# canSlaveV05a.net
KiCad netlist of a schematic drawn in EAGLE
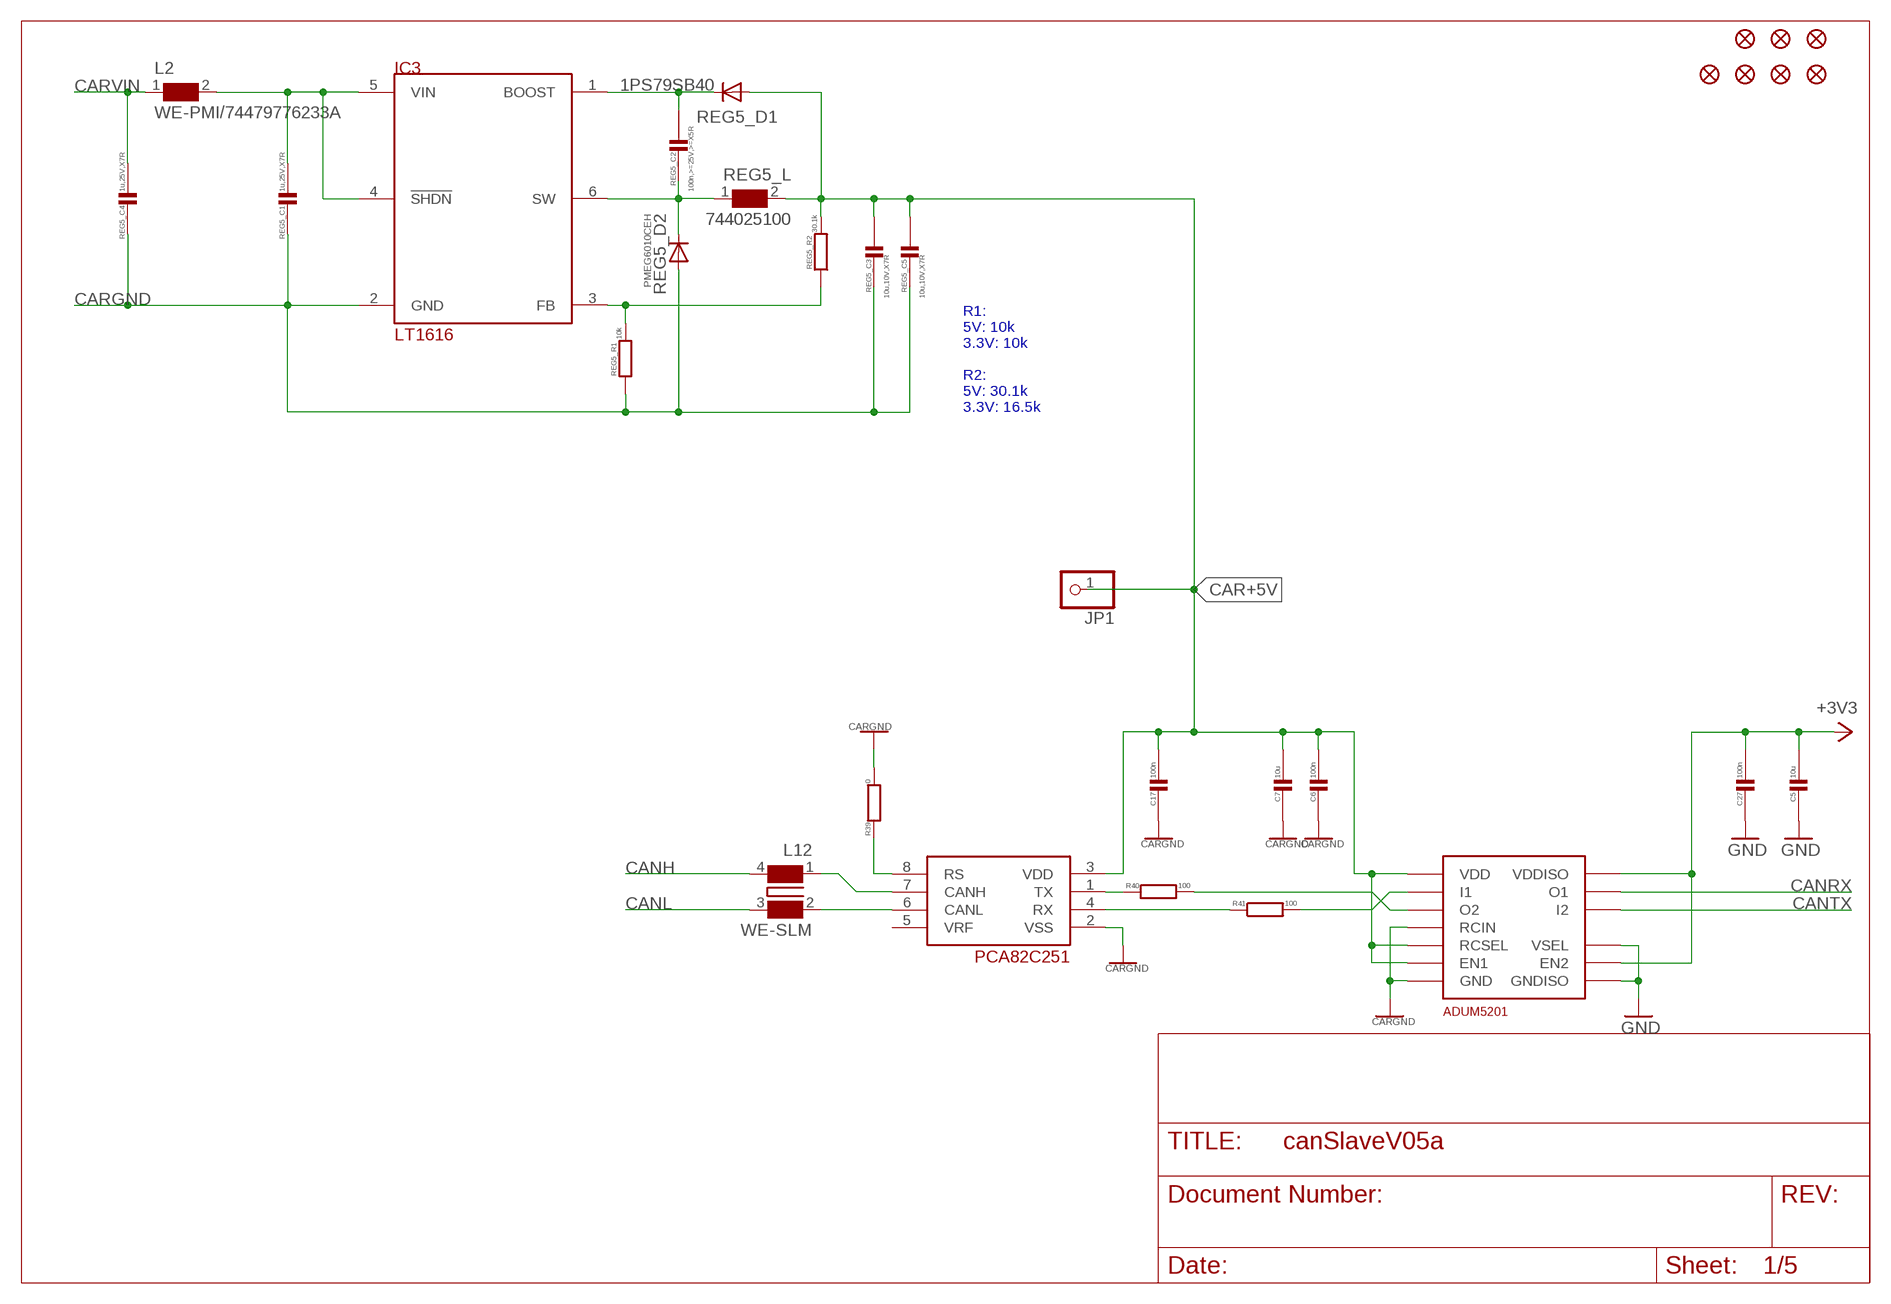
[diagram p0: schematic, sheet 1]
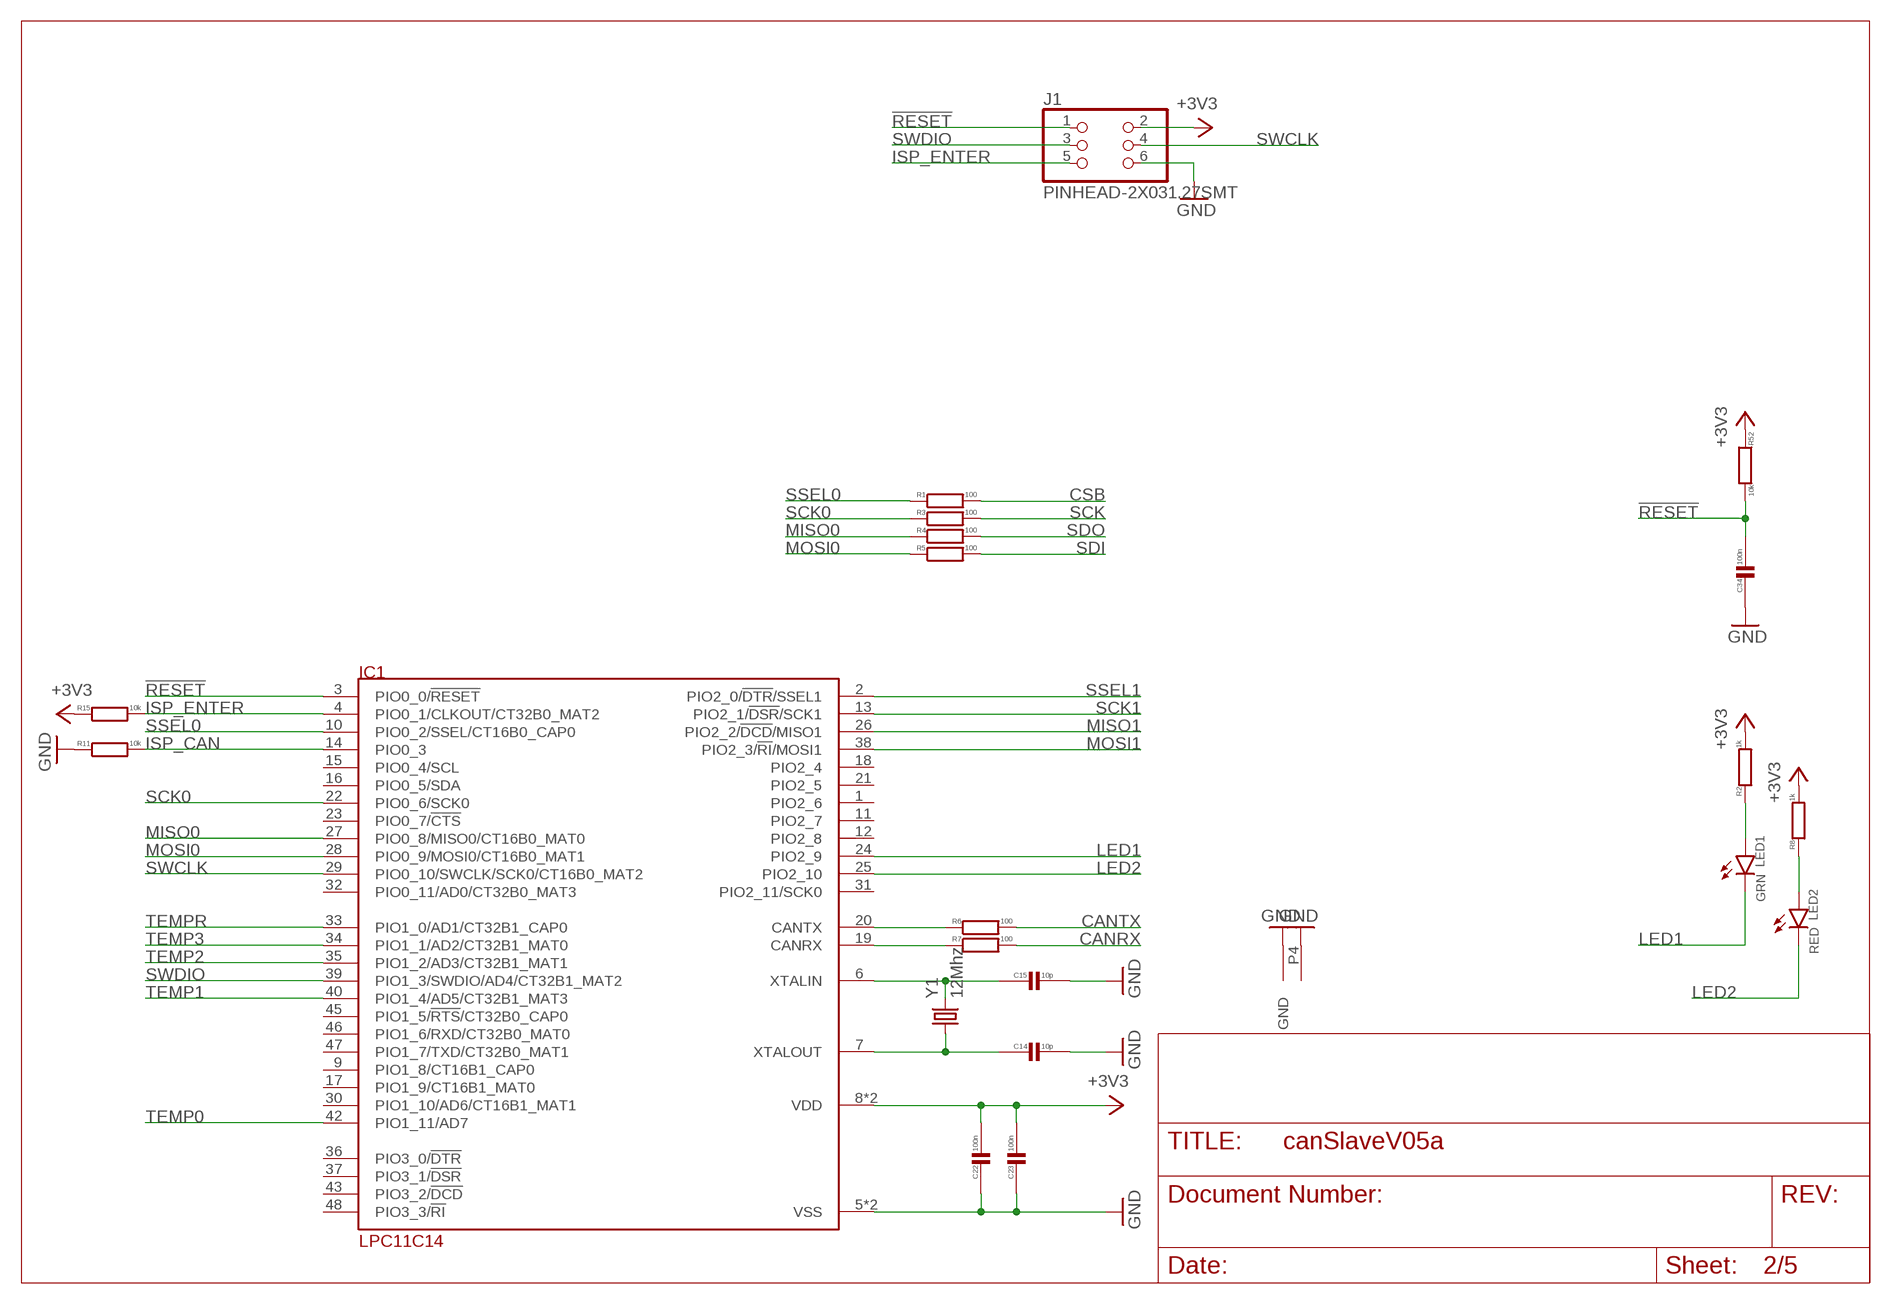
[diagram p1: schematic, sheet 2]
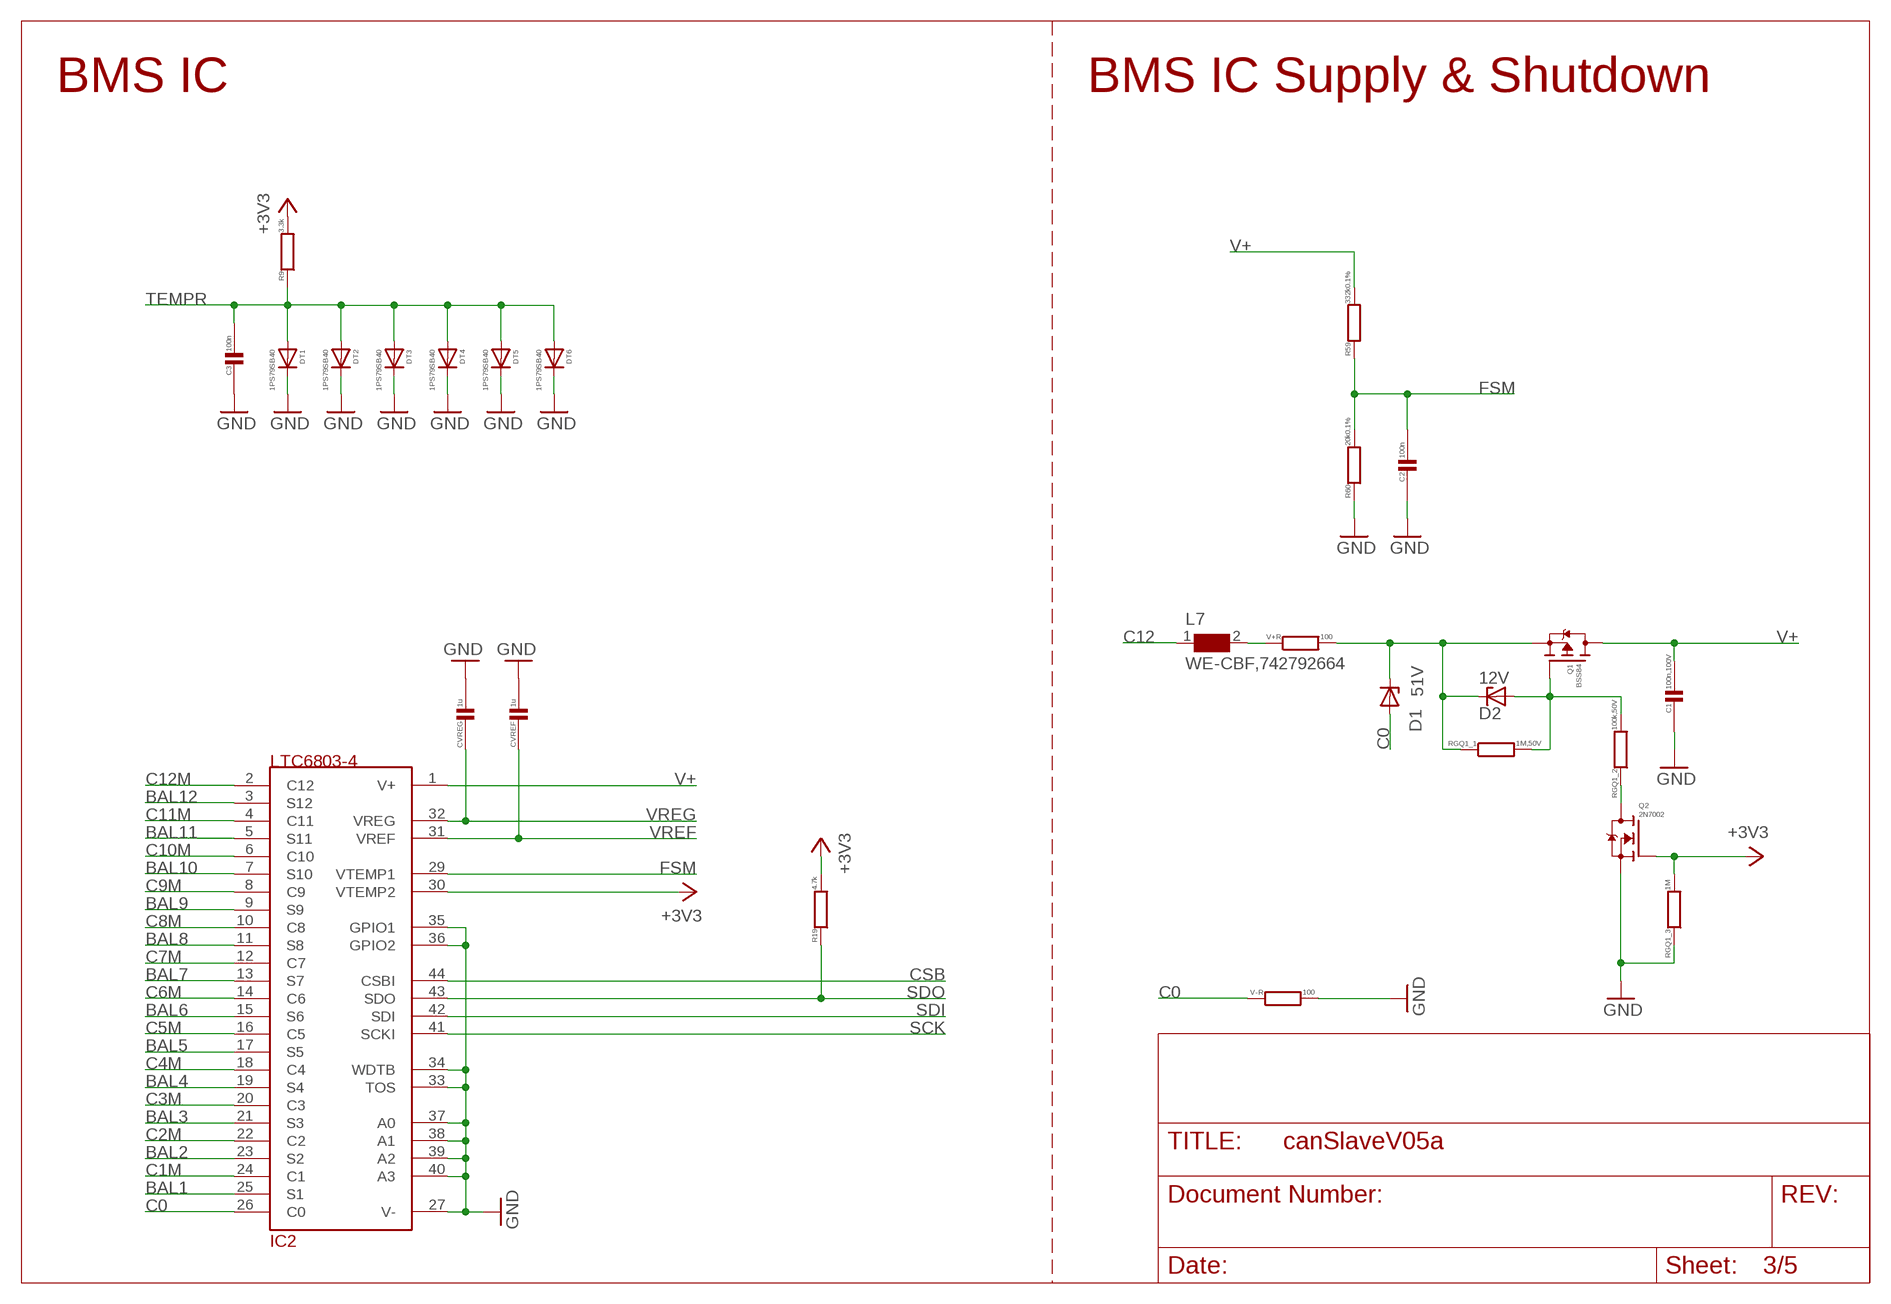
[diagram p2: schematic, sheet 3]
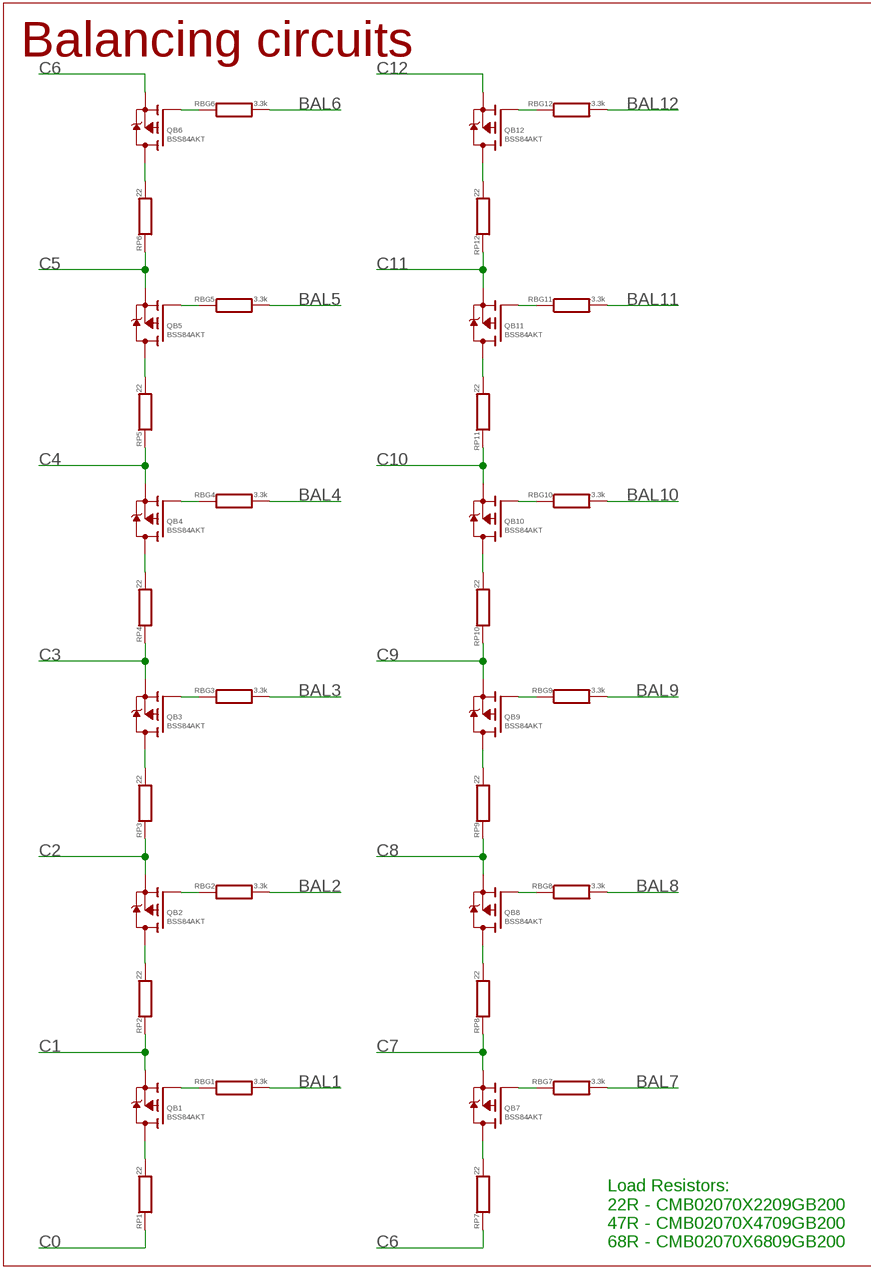
[diagram p3: schematic, sheet 4, part 1 of 2]
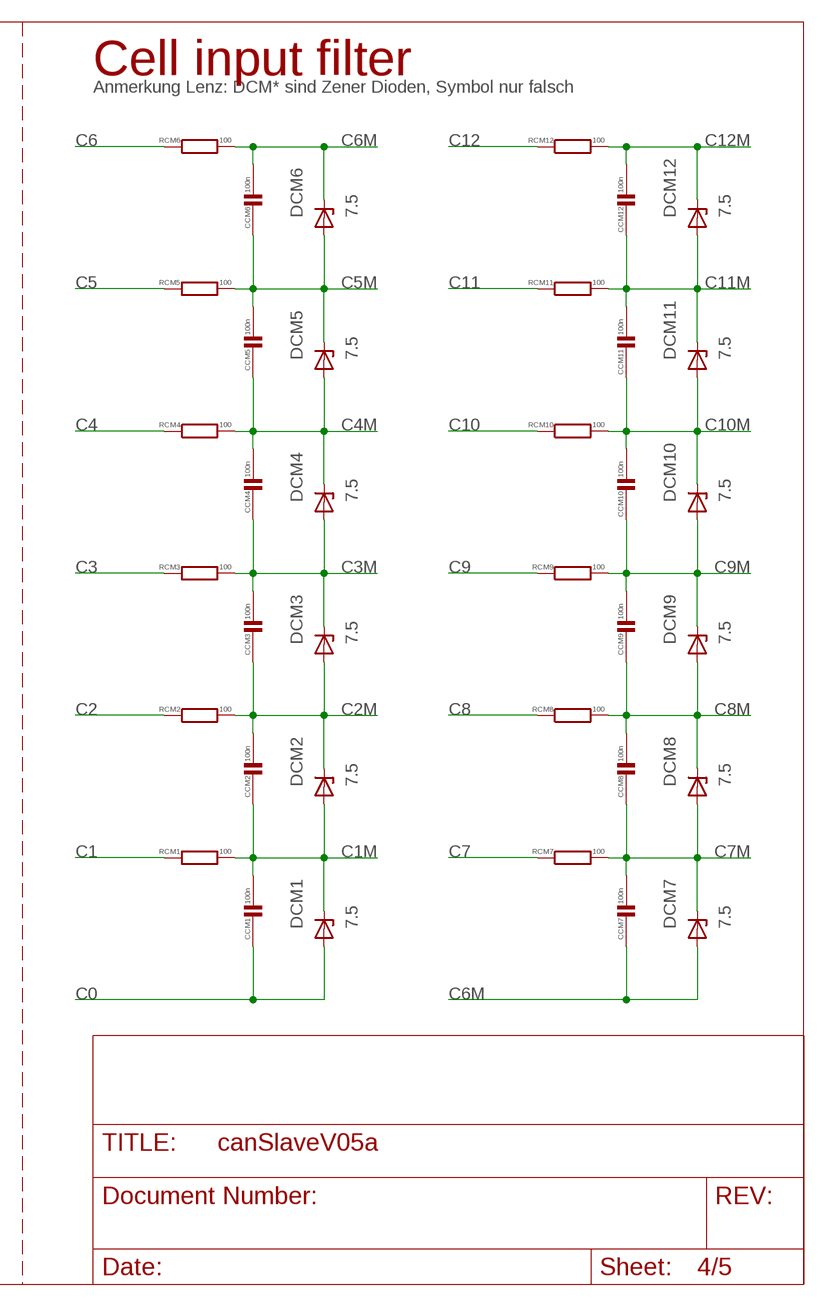
[diagram p4: schematic, sheet 4, part 2 of 2]
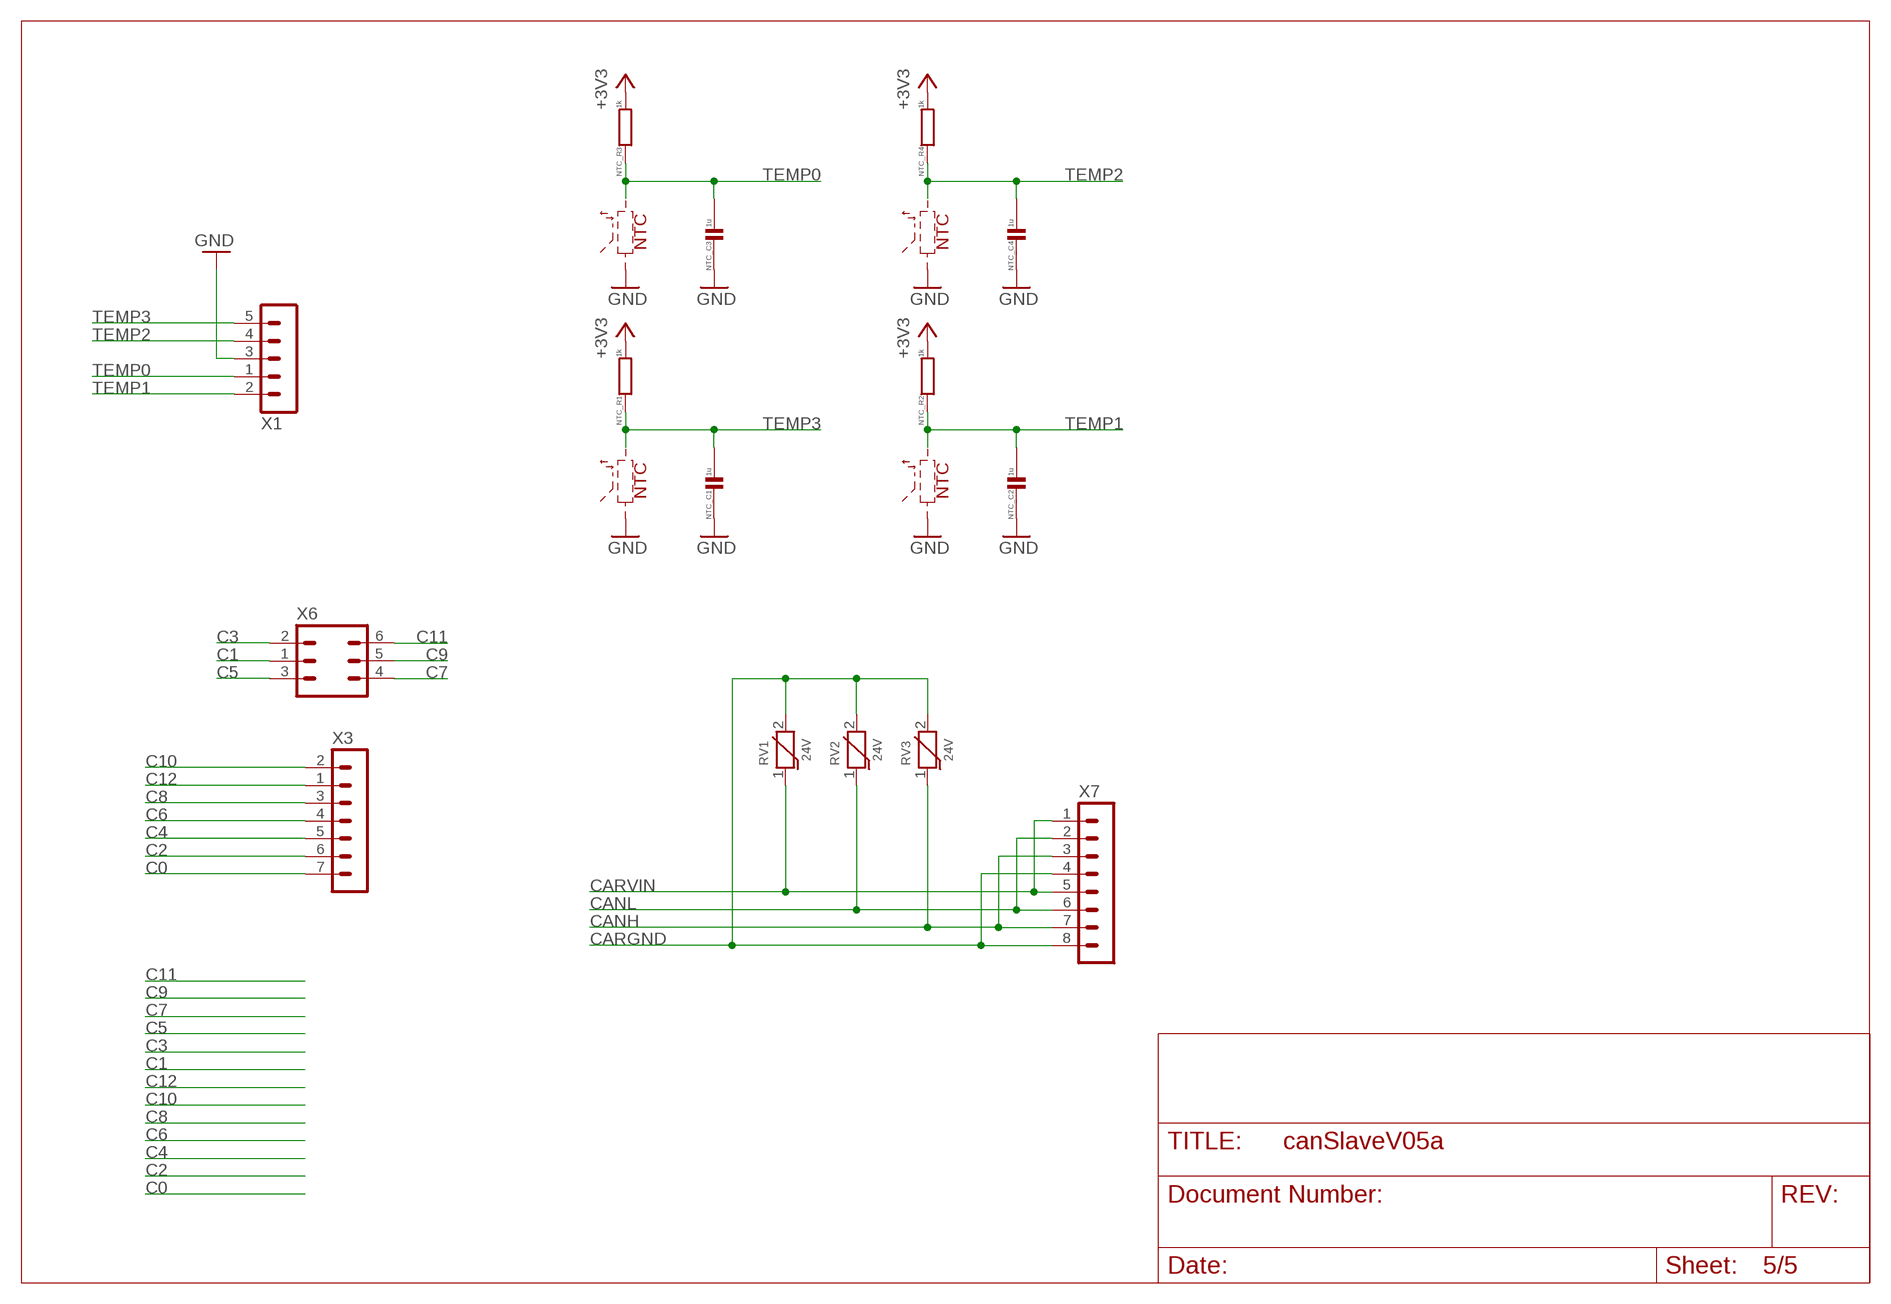
[diagram p5: schematic, sheet 5]

(export (version "E")
  (design (tool "Eeschema 10.0.6"))
  (components
    (comp (ref "C5")
      (value "10u")
      (footprint "eagle-import:C0603")
      (libsource (lib "eagle-import") (part "C0603"))
    )
    (comp (ref "C6")
      (value "100n")
      (footprint "eagle-import:C0402")
      (libsource (lib "eagle-import") (part "C0402"))
    )
    (comp (ref "C7")
      (value "10u")
      (footprint "eagle-import:C0603")
      (libsource (lib "eagle-import") (part "C0603"))
    )
    (comp (ref "C17")
      (value "100n")
      (footprint "eagle-import:C0402")
      (libsource (lib "eagle-import") (part "C0402"))
    )
    (comp (ref "C27")
      (value "100n")
      (footprint "eagle-import:C0402")
      (libsource (lib "eagle-import") (part "C0402"))
    )
    (comp (ref "FID2")
      (value "FIDUCIAL\"\"")
      (footprint "eagle-import:FIDUCIAL_1MM")
      (libsource (lib "eagle-import") (part "FIDUCIAL{dblquote}{dblquote}"))
    )
    (comp (ref "FID3")
      (value "FIDUCIAL\"\"")
      (footprint "eagle-import:FIDUCIAL_1MM")
      (libsource (lib "eagle-import") (part "FIDUCIAL{dblquote}{dblquote}"))
    )
    (comp (ref "FID4")
      (value "FIDUCIAL\"\"")
      (footprint "eagle-import:FIDUCIAL_1MM")
      (libsource (lib "eagle-import") (part "FIDUCIAL{dblquote}{dblquote}"))
    )
    (comp (ref "FID7")
      (value "FIDUCIAL\"\"")
      (footprint "eagle-import:FIDUCIAL_1MM")
      (libsource (lib "eagle-import") (part "FIDUCIAL{dblquote}{dblquote}"))
    )
    (comp (ref "FID8")
      (value "FIDUCIAL\"\"")
      (footprint "eagle-import:FIDUCIAL_1MM")
      (libsource (lib "eagle-import") (part "FIDUCIAL{dblquote}{dblquote}"))
    )
    (comp (ref "FID9")
      (value "FIDUCIAL\"\"")
      (footprint "eagle-import:FIDUCIAL_1MM")
      (libsource (lib "eagle-import") (part "FIDUCIAL{dblquote}{dblquote}"))
    )
    (comp (ref "FID10")
      (value "FIDUCIAL\"\"")
      (footprint "eagle-import:FIDUCIAL_1MM")
      (libsource (lib "eagle-import") (part "FIDUCIAL{dblquote}{dblquote}"))
    )
    (comp (ref "IC3")
      (value "LT1616")
      (footprint "eagle-import:SOT23-6")
      (libsource (lib "eagle-import") (part "LT1616"))
    )
    (comp (ref "IC5")
      (value "PCA82C251")
      (footprint "eagle-import:SO-8")
      (libsource (lib "eagle-import") (part "MCP2551"))
    )
    (comp (ref "JP1")
      (value "PINHD-1X1")
      (footprint "eagle-import:1X01")
      (libsource (lib "eagle-import") (part "PINHD-1X1"))
    )
    (comp (ref "L2")
      (value "WE-PMI/74479776233A")
      (footprint "eagle-import:WE-PMI_0806")
      (libsource (lib "eagle-import") (part "WE-PMI_0806"))
    )
    (comp (ref "L12")
      (value "WE-SLM")
      (footprint "eagle-import:WE-SLM")
      (libsource (lib "eagle-import") (part "WE-SLM"))
    )
    (comp (ref "R39")
      (value "0")
      (footprint "eagle-import:R0402")
      (libsource (lib "eagle-import") (part "R0402"))
    )
    (comp (ref "R40")
      (value "100")
      (footprint "eagle-import:R0402")
      (libsource (lib "eagle-import") (part "R0402"))
    )
    (comp (ref "R41")
      (value "100")
      (footprint "eagle-import:R0402")
      (libsource (lib "eagle-import") (part "R0402"))
    )
    (comp (ref "REG5_C1")
      (value "1u,25V,X7R")
      (footprint "eagle-import:C0805")
      (libsource (lib "eagle-import") (part "C0805"))
    )
    (comp (ref "REG5_C2")
      (value "100n,>=25V,>=X5R")
      (footprint "eagle-import:C0402")
      (libsource (lib "eagle-import") (part "C0402"))
    )
    (comp (ref "REG5_C3")
      (value "10u,10V,X7R")
      (footprint "eagle-import:C0805")
      (libsource (lib "eagle-import") (part "C0805"))
    )
    (comp (ref "REG5_C4")
      (value "1u,25V,X7R")
      (footprint "eagle-import:C0805")
      (libsource (lib "eagle-import") (part "C0805"))
    )
    (comp (ref "REG5_C5")
      (value "10u,10V,X7R")
      (footprint "eagle-import:C0805")
      (libsource (lib "eagle-import") (part "C0805"))
    )
    (comp (ref "REG5_D1")
      (value "1PS79SB40")
      (footprint "eagle-import:SOD523")
      (libsource (lib "eagle-import") (part "DIODE-SOD523"))
    )
    (comp (ref "REG5_D2")
      (value "PMEG6010CEH")
      (footprint "eagle-import:SOD123")
      (libsource (lib "eagle-import") (part "D-SOD123"))
    )
    (comp (ref "REG5_L")
      (value "744025100")
      (footprint "eagle-import:WE-TPC_2828")
      (libsource (lib "eagle-import") (part "WE-TPC_2828"))
    )
    (comp (ref "REG5_R1")
      (value "10k")
      (footprint "eagle-import:R0402")
      (libsource (lib "eagle-import") (part "R0402"))
    )
    (comp (ref "REG5_R2")
      (value "30.1k")
      (footprint "eagle-import:R0402")
      (libsource (lib "eagle-import") (part "R0402"))
    )
    (comp (ref "U$2")
      (value "ADUM5201")
      (footprint "eagle-import:SO16WB")
      (libsource (lib "eagle-import") (part "ADUM5201"))
    )
    (comp (ref "CCM1")
      (value "100n")
      (footprint "eagle-import:C0402")
      (libsource (lib "eagle-import") (part "C0402"))
    )
    (comp (ref "CCM2")
      (value "100n")
      (footprint "eagle-import:C0402")
      (libsource (lib "eagle-import") (part "C0402"))
    )
    (comp (ref "CCM3")
      (value "100n")
      (footprint "eagle-import:C0402")
      (libsource (lib "eagle-import") (part "C0402"))
    )
    (comp (ref "CCM4")
      (value "100n")
      (footprint "eagle-import:C0402")
      (libsource (lib "eagle-import") (part "C0402"))
    )
    (comp (ref "CCM5")
      (value "100n")
      (footprint "eagle-import:C0402")
      (libsource (lib "eagle-import") (part "C0402"))
    )
    (comp (ref "CCM6")
      (value "100n")
      (footprint "eagle-import:C0402")
      (libsource (lib "eagle-import") (part "C0402"))
    )
    (comp (ref "CCM7")
      (value "100n")
      (footprint "eagle-import:C0402")
      (libsource (lib "eagle-import") (part "C0402"))
    )
    (comp (ref "CCM8")
      (value "100n")
      (footprint "eagle-import:C0402")
      (libsource (lib "eagle-import") (part "C0402"))
    )
    (comp (ref "CCM9")
      (value "100n")
      (footprint "eagle-import:C0402")
      (libsource (lib "eagle-import") (part "C0402"))
    )
    (comp (ref "CCM10")
      (value "100n")
      (footprint "eagle-import:C0402")
      (libsource (lib "eagle-import") (part "C0402"))
    )
    (comp (ref "CCM11")
      (value "100n")
      (footprint "eagle-import:C0402")
      (libsource (lib "eagle-import") (part "C0402"))
    )
    (comp (ref "CCM12")
      (value "100n")
      (footprint "eagle-import:C0402")
      (libsource (lib "eagle-import") (part "C0402"))
    )
    (comp (ref "DCM1")
      (value "7.5")
      (footprint "eagle-import:SOD523")
      (libsource (lib "eagle-import") (part "ZENERSOD523"))
    )
    (comp (ref "DCM2")
      (value "7.5")
      (footprint "eagle-import:SOD523")
      (libsource (lib "eagle-import") (part "ZENERSOD523"))
    )
    (comp (ref "DCM3")
      (value "7.5")
      (footprint "eagle-import:SOD523")
      (libsource (lib "eagle-import") (part "ZENERSOD523"))
    )
    (comp (ref "DCM4")
      (value "7.5")
      (footprint "eagle-import:SOD523")
      (libsource (lib "eagle-import") (part "ZENERSOD523"))
    )
    (comp (ref "DCM5")
      (value "7.5")
      (footprint "eagle-import:SOD523")
      (libsource (lib "eagle-import") (part "ZENERSOD523"))
    )
    (comp (ref "DCM6")
      (value "7.5")
      (footprint "eagle-import:SOD523")
      (libsource (lib "eagle-import") (part "ZENERSOD523"))
    )
    (comp (ref "DCM7")
      (value "7.5")
      (footprint "eagle-import:SOD523")
      (libsource (lib "eagle-import") (part "ZENERSOD523"))
    )
    (comp (ref "DCM8")
      (value "7.5")
      (footprint "eagle-import:SOD523")
      (libsource (lib "eagle-import") (part "ZENERSOD523"))
    )
    (comp (ref "DCM9")
      (value "7.5")
      (footprint "eagle-import:SOD523")
      (libsource (lib "eagle-import") (part "ZENERSOD523"))
    )
    (comp (ref "DCM10")
      (value "7.5")
      (footprint "eagle-import:SOD523")
      (libsource (lib "eagle-import") (part "ZENERSOD523"))
    )
    (comp (ref "DCM11")
      (value "7.5")
      (footprint "eagle-import:SOD523")
      (libsource (lib "eagle-import") (part "ZENERSOD523"))
    )
    (comp (ref "DCM12")
      (value "7.5")
      (footprint "eagle-import:SOD523")
      (libsource (lib "eagle-import") (part "ZENERSOD523"))
    )
    (comp (ref "QB1")
      (value "BSS84AKT")
      (footprint "eagle-import:SOT416")
      (libsource (lib "eagle-import") (part "BSS84AKT"))
    )
    (comp (ref "QB2")
      (value "BSS84AKT")
      (footprint "eagle-import:SOT416")
      (libsource (lib "eagle-import") (part "BSS84AKT"))
    )
    (comp (ref "QB3")
      (value "BSS84AKT")
      (footprint "eagle-import:SOT416")
      (libsource (lib "eagle-import") (part "BSS84AKT"))
    )
    (comp (ref "QB4")
      (value "BSS84AKT")
      (footprint "eagle-import:SOT416")
      (libsource (lib "eagle-import") (part "BSS84AKT"))
    )
    (comp (ref "QB5")
      (value "BSS84AKT")
      (footprint "eagle-import:SOT416")
      (libsource (lib "eagle-import") (part "BSS84AKT"))
    )
    (comp (ref "QB6")
      (value "BSS84AKT")
      (footprint "eagle-import:SOT416")
      (libsource (lib "eagle-import") (part "BSS84AKT"))
    )
    (comp (ref "QB7")
      (value "BSS84AKT")
      (footprint "eagle-import:SOT416")
      (libsource (lib "eagle-import") (part "BSS84AKT"))
    )
    (comp (ref "QB8")
      (value "BSS84AKT")
      (footprint "eagle-import:SOT416")
      (libsource (lib "eagle-import") (part "BSS84AKT"))
    )
    (comp (ref "QB9")
      (value "BSS84AKT")
      (footprint "eagle-import:SOT416")
      (libsource (lib "eagle-import") (part "BSS84AKT"))
    )
    (comp (ref "QB10")
      (value "BSS84AKT")
      (footprint "eagle-import:SOT416")
      (libsource (lib "eagle-import") (part "BSS84AKT"))
    )
    (comp (ref "QB11")
      (value "BSS84AKT")
      (footprint "eagle-import:SOT416")
      (libsource (lib "eagle-import") (part "BSS84AKT"))
    )
    (comp (ref "QB12")
      (value "BSS84AKT")
      (footprint "eagle-import:SOT416")
      (libsource (lib "eagle-import") (part "BSS84AKT"))
    )
    (comp (ref "RBG1")
      (value "3.3k")
      (footprint "eagle-import:R0402")
      (libsource (lib "eagle-import") (part "R0402"))
    )
    (comp (ref "RBG2")
      (value "3.3k")
      (footprint "eagle-import:R0402")
      (libsource (lib "eagle-import") (part "R0402"))
    )
    (comp (ref "RBG3")
      (value "3.3k")
      (footprint "eagle-import:R0402")
      (libsource (lib "eagle-import") (part "R0402"))
    )
    (comp (ref "RBG4")
      (value "3.3k")
      (footprint "eagle-import:R0402")
      (libsource (lib "eagle-import") (part "R0402"))
    )
    (comp (ref "RBG5")
      (value "3.3k")
      (footprint "eagle-import:R0402")
      (libsource (lib "eagle-import") (part "R0402"))
    )
    (comp (ref "RBG6")
      (value "3.3k")
      (footprint "eagle-import:R0402")
      (libsource (lib "eagle-import") (part "R0402"))
    )
    (comp (ref "RBG7")
      (value "3.3k")
      (footprint "eagle-import:R0402")
      (libsource (lib "eagle-import") (part "R0402"))
    )
    (comp (ref "RBG8")
      (value "3.3k")
      (footprint "eagle-import:R0402")
      (libsource (lib "eagle-import") (part "R0402"))
    )
    (comp (ref "RBG9")
      (value "3.3k")
      (footprint "eagle-import:R0402")
      (libsource (lib "eagle-import") (part "R0402"))
    )
    (comp (ref "RBG10")
      (value "3.3k")
      (footprint "eagle-import:R0402")
      (libsource (lib "eagle-import") (part "R0402"))
    )
    (comp (ref "RBG11")
      (value "3.3k")
      (footprint "eagle-import:R0402")
      (libsource (lib "eagle-import") (part "R0402"))
    )
    (comp (ref "RBG12")
      (value "3.3k")
      (footprint "eagle-import:R0402")
      (libsource (lib "eagle-import") (part "R0402"))
    )
    (comp (ref "RCM1")
      (value "100")
      (footprint "eagle-import:R0402")
      (libsource (lib "eagle-import") (part "R0402"))
    )
    (comp (ref "RCM2")
      (value "100")
      (footprint "eagle-import:R0402")
      (libsource (lib "eagle-import") (part "R0402"))
    )
    (comp (ref "RCM3")
      (value "100")
      (footprint "eagle-import:R0402")
      (libsource (lib "eagle-import") (part "R0402"))
    )
    (comp (ref "RCM4")
      (value "100")
      (footprint "eagle-import:R0402")
      (libsource (lib "eagle-import") (part "R0402"))
    )
    (comp (ref "RCM5")
      (value "100")
      (footprint "eagle-import:R0402")
      (libsource (lib "eagle-import") (part "R0402"))
    )
    (comp (ref "RCM6")
      (value "100")
      (footprint "eagle-import:R0402")
      (libsource (lib "eagle-import") (part "R0402"))
    )
    (comp (ref "RCM7")
      (value "100")
      (footprint "eagle-import:R0402")
      (libsource (lib "eagle-import") (part "R0402"))
    )
    (comp (ref "RCM8")
      (value "100")
      (footprint "eagle-import:R0402")
      (libsource (lib "eagle-import") (part "R0402"))
    )
    (comp (ref "RCM9")
      (value "100")
      (footprint "eagle-import:R0402")
      (libsource (lib "eagle-import") (part "R0402"))
    )
    (comp (ref "RCM10")
      (value "100")
      (footprint "eagle-import:R0402")
      (libsource (lib "eagle-import") (part "R0402"))
    )
    (comp (ref "RCM11")
      (value "100")
      (footprint "eagle-import:R0402")
      (libsource (lib "eagle-import") (part "R0402"))
    )
    (comp (ref "RCM12")
      (value "100")
      (footprint "eagle-import:R0402")
      (libsource (lib "eagle-import") (part "R0402"))
    )
    (comp (ref "RP1")
      (value "22")
      (footprint "eagle-import:MINI_MELF-0207R")
      (libsource (lib "eagle-import") (part "RMELF-0207R"))
    )
    (comp (ref "RP2")
      (value "22")
      (footprint "eagle-import:MINI_MELF-0207R")
      (libsource (lib "eagle-import") (part "RMELF-0207R"))
    )
    (comp (ref "RP3")
      (value "22")
      (footprint "eagle-import:MINI_MELF-0207R")
      (libsource (lib "eagle-import") (part "RMELF-0207R"))
    )
    (comp (ref "RP4")
      (value "22")
      (footprint "eagle-import:MINI_MELF-0207R")
      (libsource (lib "eagle-import") (part "RMELF-0207R"))
    )
    (comp (ref "RP5")
      (value "22")
      (footprint "eagle-import:MINI_MELF-0207R")
      (libsource (lib "eagle-import") (part "RMELF-0207R"))
    )
    (comp (ref "RP6")
      (value "22")
      (footprint "eagle-import:MINI_MELF-0207R")
      (libsource (lib "eagle-import") (part "RMELF-0207R"))
    )
    (comp (ref "RP7")
      (value "22")
      (footprint "eagle-import:MINI_MELF-0207R")
      (libsource (lib "eagle-import") (part "RMELF-0207R"))
    )
    (comp (ref "RP8")
      (value "22")
      (footprint "eagle-import:MINI_MELF-0207R")
      (libsource (lib "eagle-import") (part "RMELF-0207R"))
    )
    (comp (ref "RP9")
      (value "22")
      (footprint "eagle-import:MINI_MELF-0207R")
      (libsource (lib "eagle-import") (part "RMELF-0207R"))
    )
    (comp (ref "RP10")
      (value "22")
      (footprint "eagle-import:MINI_MELF-0207R")
      (libsource (lib "eagle-import") (part "RMELF-0207R"))
    )
    (comp (ref "RP11")
      (value "22")
      (footprint "eagle-import:MINI_MELF-0207R")
      (libsource (lib "eagle-import") (part "RMELF-0207R"))
    )
    (comp (ref "RP12")
      (value "22")
      (footprint "eagle-import:MINI_MELF-0207R")
      (libsource (lib "eagle-import") (part "RMELF-0207R"))
    )
    (comp (ref "C14")
      (value "10p")
      (footprint "eagle-import:C0402")
      (libsource (lib "eagle-import") (part "C0402"))
    )
    (comp (ref "C15")
      (value "10p")
      (footprint "eagle-import:C0402")
      (libsource (lib "eagle-import") (part "C0402"))
    )
    (comp (ref "C22")
      (value "100n")
      (footprint "eagle-import:C0402")
      (libsource (lib "eagle-import") (part "C0402"))
    )
    (comp (ref "C23")
      (value "100n")
      (footprint "eagle-import:C0402")
      (libsource (lib "eagle-import") (part "C0402"))
    )
    (comp (ref "C34")
      (value "100n")
      (footprint "eagle-import:C0402")
      (libsource (lib "eagle-import") (part "C0402"))
    )
    (comp (ref "IC1")
      (value "LPC11C14")
      (footprint "eagle-import:LQFP48")
      (libsource (lib "eagle-import") (part "LPC11C1X"))
    )
    (comp (ref "J1")
      (value "PINHEAD-2X031.27SMT")
      (footprint "eagle-import:2X03_1.27MM_SMT")
      (libsource (lib "eagle-import") (part "PINHEAD-2X031.27SMT"))
    )
    (comp (ref "LED1")
      (value "GRN")
      (footprint "eagle-import:CHIPLED_0603")
      (libsource (lib "eagle-import") (part "LED0603"))
    )
    (comp (ref "LED2")
      (value "RED")
      (footprint "eagle-import:CHIPLED_0603")
      (libsource (lib "eagle-import") (part "LED0603"))
    )
    (comp (ref "R1")
      (value "100")
      (footprint "eagle-import:R0402")
      (libsource (lib "eagle-import") (part "R0402"))
    )
    (comp (ref "R2")
      (value "1k")
      (footprint "eagle-import:R0402")
      (libsource (lib "eagle-import") (part "R0402"))
    )
    (comp (ref "R3")
      (value "100")
      (footprint "eagle-import:R0402")
      (libsource (lib "eagle-import") (part "R0402"))
    )
    (comp (ref "R4")
      (value "100")
      (footprint "eagle-import:R0402")
      (libsource (lib "eagle-import") (part "R0402"))
    )
    (comp (ref "R5")
      (value "100")
      (footprint "eagle-import:R0402")
      (libsource (lib "eagle-import") (part "R0402"))
    )
    (comp (ref "R6")
      (value "100")
      (footprint "eagle-import:R0402")
      (libsource (lib "eagle-import") (part "R0402"))
    )
    (comp (ref "R7")
      (value "100")
      (footprint "eagle-import:R0402")
      (libsource (lib "eagle-import") (part "R0402"))
    )
    (comp (ref "R8")
      (value "1k")
      (footprint "eagle-import:R0402")
      (libsource (lib "eagle-import") (part "R0402"))
    )
    (comp (ref "R11")
      (value "10k")
      (footprint "eagle-import:R0402")
      (libsource (lib "eagle-import") (part "R0402"))
    )
    (comp (ref "R15")
      (value "10k")
      (footprint "eagle-import:R0402")
      (libsource (lib "eagle-import") (part "R0402"))
    )
    (comp (ref "R52")
      (value "10k")
      (footprint "eagle-import:R0402")
      (libsource (lib "eagle-import") (part "R0402"))
    )
    (comp (ref "Y1")
      (value "12Mhz")
      (footprint "eagle-import:MT")
      (libsource (lib "eagle-import") (part "CRYSTAL43.2X2.5"))
    )
    (comp (ref "NTC_C1")
      (value "1u")
      (footprint "eagle-import:C0402")
      (libsource (lib "eagle-import") (part "C0402"))
    )
    (comp (ref "NTC_C2")
      (value "1u")
      (footprint "eagle-import:C0402")
      (libsource (lib "eagle-import") (part "C0402"))
    )
    (comp (ref "NTC_C3")
      (value "1u")
      (footprint "eagle-import:C0402")
      (libsource (lib "eagle-import") (part "C0402"))
    )
    (comp (ref "NTC_C4")
      (value "1u")
      (footprint "eagle-import:C0402")
      (libsource (lib "eagle-import") (part "C0402"))
    )
    (comp (ref "NTC_R1")
      (value "1k")
      (footprint "eagle-import:R0402")
      (libsource (lib "eagle-import") (part "R0402"))
    )
    (comp (ref "NTC_R2")
      (value "1k")
      (footprint "eagle-import:R0402")
      (libsource (lib "eagle-import") (part "R0402"))
    )
    (comp (ref "NTC_R3")
      (value "1k")
      (footprint "eagle-import:R0402")
      (libsource (lib "eagle-import") (part "R0402"))
    )
    (comp (ref "NTC_R4")
      (value "1k")
      (footprint "eagle-import:R0402")
      (libsource (lib "eagle-import") (part "R0402"))
    )
    (comp (ref "RV1")
      (value "24V")
      (footprint "eagle-import:R0805")
      (libsource (lib "eagle-import") (part "VARISTOR0805"))
    )
    (comp (ref "RV2")
      (value "24V")
      (footprint "eagle-import:R0603")
      (libsource (lib "eagle-import") (part "VARISTOR0603"))
    )
    (comp (ref "RV3")
      (value "24V")
      (footprint "eagle-import:R0603")
      (libsource (lib "eagle-import") (part "VARISTOR0603"))
    )
    (comp (ref "X1")
      (value "HEADER_POS5_43650-0509")
      (footprint "eagle-import:43650-0509")
      (libsource (lib "eagle-import") (part "HEADER_POS5_?43650-0509"))
    )
    (comp (ref "X3")
      (value "HEADER_POS7_43650-0709")
      (footprint "eagle-import:43650-0709")
      (libsource (lib "eagle-import") (part "HEADER_POS7_?43650-0709"))
    )
    (comp (ref "X6")
      (value "HEADER_POS6_43650-0609")
      (footprint "eagle-import:43650-0609")
      (libsource (lib "eagle-import") (part "HEADER_POS6_?43650-0609"))
    )
    (comp (ref "X7")
      (value "HEADER_POS8_43045-0800")
      (footprint "eagle-import:43045-0800")
      (libsource (lib "eagle-import") (part "HEADER_POS8_?43045-0800"))
    )
    (comp (ref "C1")
      (value "100n,100V")
      (footprint "eagle-import:C0603")
      (libsource (lib "eagle-import") (part "C0603"))
    )
    (comp (ref "C2")
      (value "100n")
      (footprint "eagle-import:C0402")
      (libsource (lib "eagle-import") (part "C0402"))
    )
    (comp (ref "C3")
      (value "100n")
      (footprint "eagle-import:C0402")
      (libsource (lib "eagle-import") (part "C0402"))
    )
    (comp (ref "CVREF")
      (value "1u")
      (footprint "eagle-import:C0402")
      (libsource (lib "eagle-import") (part "C0402"))
    )
    (comp (ref "CVREG")
      (value "1u")
      (footprint "eagle-import:C0402")
      (libsource (lib "eagle-import") (part "C0402"))
    )
    (comp (ref "D1")
      (value "51V")
      (footprint "eagle-import:SOD323-L")
      (libsource (lib "eagle-import") (part "ZENERSOD323"))
    )
    (comp (ref "D2")
      (value "12V")
      (footprint "eagle-import:SOD323-L")
      (libsource (lib "eagle-import") (part "ZENERSOD323"))
    )
    (comp (ref "DT1")
      (value "1PS79SB40")
      (footprint "eagle-import:SOD523")
      (libsource (lib "eagle-import") (part "DIODE-SOD523"))
    )
    (comp (ref "DT2")
      (value "1PS79SB40")
      (footprint "eagle-import:SOD523")
      (libsource (lib "eagle-import") (part "DIODE-SOD523"))
    )
    (comp (ref "DT3")
      (value "1PS79SB40")
      (footprint "eagle-import:SOD523")
      (libsource (lib "eagle-import") (part "DIODE-SOD523"))
    )
    (comp (ref "DT4")
      (value "1PS79SB40")
      (footprint "eagle-import:SOD523")
      (libsource (lib "eagle-import") (part "DIODE-SOD523"))
    )
    (comp (ref "DT5")
      (value "1PS79SB40")
      (footprint "eagle-import:SOD523")
      (libsource (lib "eagle-import") (part "DIODE-SOD523"))
    )
    (comp (ref "DT6")
      (value "1PS79SB40")
      (footprint "eagle-import:SOD523")
      (libsource (lib "eagle-import") (part "DIODE-SOD523"))
    )
    (comp (ref "IC2")
      (value "LTC6803-4")
      (footprint "eagle-import:44SSOP")
      (libsource (lib "eagle-import") (part "LTC6803-4"))
    )
    (comp (ref "L7")
      (value "WE-CBF,742792664")
      (footprint "eagle-import:0603")
      (libsource (lib "eagle-import") (part "WE-CBF_0603"))
    )
    (comp (ref "Q1")
      (value "BSS84")
      (footprint "eagle-import:SOT23")
      (libsource (lib "eagle-import") (part "BSS84"))
    )
    (comp (ref "Q2")
      (value "2N7002")
      (footprint "eagle-import:SOT23")
      (libsource (lib "eagle-import") (part "2N7002"))
    )
    (comp (ref "R9")
      (value "3.3k")
      (footprint "eagle-import:R0603")
      (libsource (lib "eagle-import") (part "R0603"))
    )
    (comp (ref "R19")
      (value "4.7k")
      (footprint "eagle-import:R0402")
      (libsource (lib "eagle-import") (part "R0402"))
    )
    (comp (ref "R59")
      (value "332k0.1%")
      (footprint "eagle-import:R0603")
      (libsource (lib "eagle-import") (part "R0603"))
    )
    (comp (ref "R60")
      (value "20k0.1%")
      (footprint "eagle-import:R0402")
      (libsource (lib "eagle-import") (part "R0402"))
    )
    (comp (ref "RGQ1_1")
      (value "1M,50V")
      (footprint "eagle-import:R0603")
      (libsource (lib "eagle-import") (part "R0603"))
    )
    (comp (ref "RGQ1_2")
      (value "100k,50V")
      (footprint "eagle-import:R0603")
      (libsource (lib "eagle-import") (part "R0603"))
    )
    (comp (ref "RGQ1_3")
      (value "1M")
      (footprint "eagle-import:R0402")
      (libsource (lib "eagle-import") (part "R0402"))
    )
    (comp (ref "V+R")
      (value "100")
      (footprint "eagle-import:R0603")
      (libsource (lib "eagle-import") (part "R0603"))
    )
    (comp (ref "V-R")
      (value "100")
      (footprint "eagle-import:R0603")
      (libsource (lib "eagle-import") (part "R0603"))
    )
  )
  (nets
    (net (code "1") (name "+3V3") (class "Default")
      (node (ref "C22") (pin "1") (pinfunction "1_1") (pintype "passive"))
      (node (ref "C23") (pin "1") (pinfunction "1_1") (pintype "passive"))
      (node (ref "C27") (pin "1") (pinfunction "1_1") (pintype "passive"))
      (node (ref "C5") (pin "1") (pinfunction "1_1") (pintype "passive"))
      (node (ref "IC1") (pin "44") (pinfunction "VDD_44") (pintype "bidirectional"))
      (node (ref "IC1") (pin "8") (pinfunction "VDD_8") (pintype "bidirectional"))
      (node (ref "IC2") (pin "30") (pinfunction "VTEMP2_30") (pintype "bidirectional"))
      (node (ref "J1") (pin "2") (pinfunction "2_2") (pintype "passive"))
      (node (ref "NTC_R1") (pin "2") (pinfunction "2_2") (pintype "passive"))
      (node (ref "NTC_R2") (pin "2") (pinfunction "2_2") (pintype "passive"))
      (node (ref "NTC_R3") (pin "2") (pinfunction "2_2") (pintype "passive"))
      (node (ref "NTC_R4") (pin "2") (pinfunction "2_2") (pintype "passive"))
      (node (ref "Q2") (pin "1") (pinfunction "G_1") (pintype "passive"))
      (node (ref "R15") (pin "1") (pinfunction "1_1") (pintype "passive"))
      (node (ref "R19") (pin "2") (pinfunction "2_2") (pintype "passive"))
      (node (ref "R2") (pin "2") (pinfunction "2_2") (pintype "passive"))
      (node (ref "R52") (pin "1") (pinfunction "1_1") (pintype "passive"))
      (node (ref "R8") (pin "2") (pinfunction "2_2") (pintype "passive"))
      (node (ref "R9") (pin "2") (pinfunction "2_2") (pintype "passive"))
      (node (ref "RGQ1_3") (pin "2") (pinfunction "2_2") (pintype "passive"))
      (node (ref "U$2") (pin "P$10") (pinfunction "EN2_P$10") (pintype "bidirectional"))
      (node (ref "U$2") (pin "P$16") (pinfunction "VDDISO_P$16") (pintype "bidirectional"))
    )
    (net (code "2") (name "BAL1") (class "Default")
      (node (ref "IC2") (pin "25") (pinfunction "S1_25") (pintype "bidirectional"))
      (node (ref "RBG1") (pin "2") (pinfunction "2_2") (pintype "passive"))
    )
    (net (code "3") (name "BAL2") (class "Default")
      (node (ref "IC2") (pin "23") (pinfunction "S2_23") (pintype "bidirectional"))
      (node (ref "RBG2") (pin "2") (pinfunction "2_2") (pintype "passive"))
    )
    (net (code "4") (name "BAL3") (class "Default")
      (node (ref "IC2") (pin "21") (pinfunction "S3_21") (pintype "bidirectional"))
      (node (ref "RBG3") (pin "2") (pinfunction "2_2") (pintype "passive"))
    )
    (net (code "5") (name "BAL4") (class "Default")
      (node (ref "IC2") (pin "19") (pinfunction "S4_19") (pintype "bidirectional"))
      (node (ref "RBG4") (pin "2") (pinfunction "2_2") (pintype "passive"))
    )
    (net (code "6") (name "BAL5") (class "Default")
      (node (ref "IC2") (pin "17") (pinfunction "S5_17") (pintype "bidirectional"))
      (node (ref "RBG5") (pin "2") (pinfunction "2_2") (pintype "passive"))
    )
    (net (code "7") (name "BAL6") (class "Default")
      (node (ref "IC2") (pin "15") (pinfunction "S6_15") (pintype "bidirectional"))
      (node (ref "RBG6") (pin "2") (pinfunction "2_2") (pintype "passive"))
    )
    (net (code "8") (name "BAL7") (class "Default")
      (node (ref "IC2") (pin "13") (pinfunction "S7_13") (pintype "bidirectional"))
      (node (ref "RBG7") (pin "2") (pinfunction "2_2") (pintype "passive"))
    )
    (net (code "9") (name "BAL8") (class "Default")
      (node (ref "IC2") (pin "11") (pinfunction "S8_11") (pintype "bidirectional"))
      (node (ref "RBG8") (pin "2") (pinfunction "2_2") (pintype "passive"))
    )
    (net (code "10") (name "BAL9") (class "Default")
      (node (ref "IC2") (pin "9") (pinfunction "S9_9") (pintype "bidirectional"))
      (node (ref "RBG9") (pin "2") (pinfunction "2_2") (pintype "passive"))
    )
    (net (code "11") (name "BAL10") (class "Default")
      (node (ref "IC2") (pin "7") (pinfunction "S10_7") (pintype "bidirectional"))
      (node (ref "RBG10") (pin "2") (pinfunction "2_2") (pintype "passive"))
    )
    (net (code "12") (name "BAL11") (class "Default")
      (node (ref "IC2") (pin "5") (pinfunction "S11_5") (pintype "bidirectional"))
      (node (ref "RBG11") (pin "2") (pinfunction "2_2") (pintype "passive"))
    )
    (net (code "13") (name "BAL12") (class "Default")
      (node (ref "IC2") (pin "3") (pinfunction "S12_3") (pintype "bidirectional"))
      (node (ref "RBG12") (pin "2") (pinfunction "2_2") (pintype "passive"))
    )
    (net (code "14") (name "C0") (class "Default")
      (node (ref "CCM1") (pin "2") (pinfunction "2_2") (pintype "passive"))
      (node (ref "D1") (pin "A") (pinfunction "A_A") (pintype "passive"))
      (node (ref "DCM1") (pin "A") (pinfunction "A_A") (pintype "passive"))
      (node (ref "IC2") (pin "26") (pinfunction "C0_26") (pintype "bidirectional"))
      (node (ref "RP1") (pin "1") (pinfunction "1_1") (pintype "passive"))
      (node (ref "V-R") (pin "1") (pinfunction "1_1") (pintype "passive"))
      (node (ref "X3") (pin "7") (pinfunction "7_7") (pintype "passive"))
    )
    (net (code "15") (name "C1") (class "Default")
      (node (ref "QB1") (pin "2") (pinfunction "S_2") (pintype "passive"))
      (node (ref "RCM1") (pin "1") (pinfunction "1_1") (pintype "passive"))
      (node (ref "RP2") (pin "1") (pinfunction "1_1") (pintype "passive"))
      (node (ref "X6") (pin "1") (pinfunction "2_1") (pintype "passive"))
    )
    (net (code "16") (name "C1M") (class "Default")
      (node (ref "CCM1") (pin "1") (pinfunction "1_1") (pintype "passive"))
      (node (ref "CCM2") (pin "2") (pinfunction "2_2") (pintype "passive"))
      (node (ref "DCM1") (pin "C") (pinfunction "C_C") (pintype "passive"))
      (node (ref "DCM2") (pin "A") (pinfunction "A_A") (pintype "passive"))
      (node (ref "IC2") (pin "24") (pinfunction "C1_24") (pintype "bidirectional"))
      (node (ref "RCM1") (pin "2") (pinfunction "2_2") (pintype "passive"))
    )
    (net (code "17") (name "C2") (class "Default")
      (node (ref "QB2") (pin "2") (pinfunction "S_2") (pintype "passive"))
      (node (ref "RCM2") (pin "1") (pinfunction "1_1") (pintype "passive"))
      (node (ref "RP3") (pin "1") (pinfunction "1_1") (pintype "passive"))
      (node (ref "X3") (pin "6") (pinfunction "6_6") (pintype "passive"))
    )
    (net (code "18") (name "C2M") (class "Default")
      (node (ref "CCM2") (pin "1") (pinfunction "1_1") (pintype "passive"))
      (node (ref "CCM3") (pin "2") (pinfunction "2_2") (pintype "passive"))
      (node (ref "DCM2") (pin "C") (pinfunction "C_C") (pintype "passive"))
      (node (ref "DCM3") (pin "A") (pinfunction "A_A") (pintype "passive"))
      (node (ref "IC2") (pin "22") (pinfunction "C2_22") (pintype "bidirectional"))
      (node (ref "RCM2") (pin "2") (pinfunction "2_2") (pintype "passive"))
    )
    (net (code "19") (name "C3") (class "Default")
      (node (ref "QB3") (pin "2") (pinfunction "S_2") (pintype "passive"))
      (node (ref "RCM3") (pin "1") (pinfunction "1_1") (pintype "passive"))
      (node (ref "RP4") (pin "1") (pinfunction "1_1") (pintype "passive"))
      (node (ref "X6") (pin "2") (pinfunction "1_2") (pintype "passive"))
    )
    (net (code "20") (name "C3M") (class "Default")
      (node (ref "CCM3") (pin "1") (pinfunction "1_1") (pintype "passive"))
      (node (ref "CCM4") (pin "2") (pinfunction "2_2") (pintype "passive"))
      (node (ref "DCM3") (pin "C") (pinfunction "C_C") (pintype "passive"))
      (node (ref "DCM4") (pin "A") (pinfunction "A_A") (pintype "passive"))
      (node (ref "IC2") (pin "20") (pinfunction "C3_20") (pintype "bidirectional"))
      (node (ref "RCM3") (pin "2") (pinfunction "2_2") (pintype "passive"))
    )
    (net (code "21") (name "C4") (class "Default")
      (node (ref "QB4") (pin "2") (pinfunction "S_2") (pintype "passive"))
      (node (ref "RCM4") (pin "1") (pinfunction "1_1") (pintype "passive"))
      (node (ref "RP5") (pin "1") (pinfunction "1_1") (pintype "passive"))
      (node (ref "X3") (pin "5") (pinfunction "5_5") (pintype "passive"))
    )
    (net (code "22") (name "C4M") (class "Default")
      (node (ref "CCM4") (pin "1") (pinfunction "1_1") (pintype "passive"))
      (node (ref "CCM5") (pin "2") (pinfunction "2_2") (pintype "passive"))
      (node (ref "DCM4") (pin "C") (pinfunction "C_C") (pintype "passive"))
      (node (ref "DCM5") (pin "A") (pinfunction "A_A") (pintype "passive"))
      (node (ref "IC2") (pin "18") (pinfunction "C4_18") (pintype "bidirectional"))
      (node (ref "RCM4") (pin "2") (pinfunction "2_2") (pintype "passive"))
    )
    (net (code "23") (name "C5") (class "Default")
      (node (ref "QB5") (pin "2") (pinfunction "S_2") (pintype "passive"))
      (node (ref "RCM5") (pin "1") (pinfunction "1_1") (pintype "passive"))
      (node (ref "RP6") (pin "1") (pinfunction "1_1") (pintype "passive"))
      (node (ref "X6") (pin "3") (pinfunction "3_3") (pintype "passive"))
    )
    (net (code "24") (name "C5M") (class "Default")
      (node (ref "CCM5") (pin "1") (pinfunction "1_1") (pintype "passive"))
      (node (ref "CCM6") (pin "2") (pinfunction "2_2") (pintype "passive"))
      (node (ref "DCM5") (pin "C") (pinfunction "C_C") (pintype "passive"))
      (node (ref "DCM6") (pin "A") (pinfunction "A_A") (pintype "passive"))
      (node (ref "IC2") (pin "16") (pinfunction "C5_16") (pintype "bidirectional"))
      (node (ref "RCM5") (pin "2") (pinfunction "2_2") (pintype "passive"))
    )
    (net (code "25") (name "C6") (class "Default")
      (node (ref "QB6") (pin "2") (pinfunction "S_2") (pintype "passive"))
      (node (ref "RCM6") (pin "1") (pinfunction "1_1") (pintype "passive"))
      (node (ref "RP7") (pin "1") (pinfunction "1_1") (pintype "passive"))
      (node (ref "X3") (pin "4") (pinfunction "4_4") (pintype "passive"))
    )
    (net (code "26") (name "C6M") (class "Default")
      (node (ref "CCM6") (pin "1") (pinfunction "1_1") (pintype "passive"))
      (node (ref "CCM7") (pin "2") (pinfunction "2_2") (pintype "passive"))
      (node (ref "DCM6") (pin "C") (pinfunction "C_C") (pintype "passive"))
      (node (ref "DCM7") (pin "A") (pinfunction "A_A") (pintype "passive"))
      (node (ref "IC2") (pin "14") (pinfunction "C6_14") (pintype "bidirectional"))
      (node (ref "RCM6") (pin "2") (pinfunction "2_2") (pintype "passive"))
    )
    (net (code "27") (name "C7") (class "Default")
      (node (ref "QB7") (pin "2") (pinfunction "S_2") (pintype "passive"))
      (node (ref "RCM7") (pin "1") (pinfunction "1_1") (pintype "passive"))
      (node (ref "RP8") (pin "1") (pinfunction "1_1") (pintype "passive"))
      (node (ref "X6") (pin "4") (pinfunction "4_4") (pintype "passive"))
    )
    (net (code "28") (name "C7M") (class "Default")
      (node (ref "CCM7") (pin "1") (pinfunction "1_1") (pintype "passive"))
      (node (ref "CCM8") (pin "2") (pinfunction "2_2") (pintype "passive"))
      (node (ref "DCM7") (pin "C") (pinfunction "C_C") (pintype "passive"))
      (node (ref "DCM8") (pin "A") (pinfunction "A_A") (pintype "passive"))
      (node (ref "IC2") (pin "12") (pinfunction "C7_12") (pintype "bidirectional"))
      (node (ref "RCM7") (pin "2") (pinfunction "2_2") (pintype "passive"))
    )
    (net (code "29") (name "C8") (class "Default")
      (node (ref "QB8") (pin "2") (pinfunction "S_2") (pintype "passive"))
      (node (ref "RCM8") (pin "1") (pinfunction "1_1") (pintype "passive"))
      (node (ref "RP9") (pin "1") (pinfunction "1_1") (pintype "passive"))
      (node (ref "X3") (pin "3") (pinfunction "3_3") (pintype "passive"))
    )
    (net (code "30") (name "C8M") (class "Default")
      (node (ref "CCM8") (pin "1") (pinfunction "1_1") (pintype "passive"))
      (node (ref "CCM9") (pin "2") (pinfunction "2_2") (pintype "passive"))
      (node (ref "DCM8") (pin "C") (pinfunction "C_C") (pintype "passive"))
      (node (ref "DCM9") (pin "A") (pinfunction "A_A") (pintype "passive"))
      (node (ref "IC2") (pin "10") (pinfunction "C8_10") (pintype "bidirectional"))
      (node (ref "RCM8") (pin "2") (pinfunction "2_2") (pintype "passive"))
    )
    (net (code "31") (name "C9") (class "Default")
      (node (ref "QB9") (pin "2") (pinfunction "S_2") (pintype "passive"))
      (node (ref "RCM9") (pin "1") (pinfunction "1_1") (pintype "passive"))
      (node (ref "RP10") (pin "1") (pinfunction "1_1") (pintype "passive"))
      (node (ref "X6") (pin "5") (pinfunction "5_5") (pintype "passive"))
    )
    (net (code "32") (name "C9M") (class "Default")
      (node (ref "CCM10") (pin "2") (pinfunction "2_2") (pintype "passive"))
      (node (ref "CCM9") (pin "1") (pinfunction "1_1") (pintype "passive"))
      (node (ref "DCM10") (pin "A") (pinfunction "A_A") (pintype "passive"))
      (node (ref "DCM9") (pin "C") (pinfunction "C_C") (pintype "passive"))
      (node (ref "IC2") (pin "8") (pinfunction "C9_8") (pintype "bidirectional"))
      (node (ref "RCM9") (pin "2") (pinfunction "2_2") (pintype "passive"))
    )
    (net (code "33") (name "C10") (class "Default")
      (node (ref "QB10") (pin "2") (pinfunction "S_2") (pintype "passive"))
      (node (ref "RCM10") (pin "1") (pinfunction "1_1") (pintype "passive"))
      (node (ref "RP11") (pin "1") (pinfunction "1_1") (pintype "passive"))
      (node (ref "X3") (pin "2") (pinfunction "1_2") (pintype "passive"))
    )
    (net (code "34") (name "C10M") (class "Default")
      (node (ref "CCM10") (pin "1") (pinfunction "1_1") (pintype "passive"))
      (node (ref "CCM11") (pin "2") (pinfunction "2_2") (pintype "passive"))
      (node (ref "DCM10") (pin "C") (pinfunction "C_C") (pintype "passive"))
      (node (ref "DCM11") (pin "A") (pinfunction "A_A") (pintype "passive"))
      (node (ref "IC2") (pin "6") (pinfunction "C10_6") (pintype "bidirectional"))
      (node (ref "RCM10") (pin "2") (pinfunction "2_2") (pintype "passive"))
    )
    (net (code "35") (name "C11") (class "Default")
      (node (ref "QB11") (pin "2") (pinfunction "S_2") (pintype "passive"))
      (node (ref "RCM11") (pin "1") (pinfunction "1_1") (pintype "passive"))
      (node (ref "RP12") (pin "1") (pinfunction "1_1") (pintype "passive"))
      (node (ref "X6") (pin "6") (pinfunction "6_6") (pintype "passive"))
    )
    (net (code "36") (name "C11M") (class "Default")
      (node (ref "CCM11") (pin "1") (pinfunction "1_1") (pintype "passive"))
      (node (ref "CCM12") (pin "2") (pinfunction "2_2") (pintype "passive"))
      (node (ref "DCM11") (pin "C") (pinfunction "C_C") (pintype "passive"))
      (node (ref "DCM12") (pin "A") (pinfunction "A_A") (pintype "passive"))
      (node (ref "IC2") (pin "4") (pinfunction "C11_4") (pintype "bidirectional"))
      (node (ref "RCM11") (pin "2") (pinfunction "2_2") (pintype "passive"))
    )
    (net (code "37") (name "C12") (class "Default")
      (node (ref "L7") (pin "1") (pinfunction "1_1") (pintype "passive"))
      (node (ref "QB12") (pin "2") (pinfunction "S_2") (pintype "passive"))
      (node (ref "RCM12") (pin "1") (pinfunction "1_1") (pintype "passive"))
      (node (ref "X3") (pin "1") (pinfunction "2_1") (pintype "passive"))
    )
    (net (code "38") (name "C12M") (class "Default")
      (node (ref "CCM12") (pin "1") (pinfunction "1_1") (pintype "passive"))
      (node (ref "DCM12") (pin "C") (pinfunction "C_C") (pintype "passive"))
      (node (ref "IC2") (pin "2") (pinfunction "C12_2") (pintype "bidirectional"))
      (node (ref "RCM12") (pin "2") (pinfunction "2_2") (pintype "passive"))
    )
    (net (code "39") (name "CANH") (class "Default")
      (node (ref "L12") (pin "4") (pinfunction "4_4") (pintype "passive"))
      (node (ref "RV3") (pin "1") (pinfunction "1_1") (pintype "passive"))
      (node (ref "X7") (pin "3") (pinfunction "3_3") (pintype "passive"))
      (node (ref "X7") (pin "7") (pinfunction "7_7") (pintype "passive"))
    )
    (net (code "40") (name "CANL") (class "Default")
      (node (ref "L12") (pin "3") (pinfunction "2_3") (pintype "passive"))
      (node (ref "RV2") (pin "1") (pinfunction "1_1") (pintype "passive"))
      (node (ref "X7") (pin "2") (pinfunction "2_2") (pintype "passive"))
      (node (ref "X7") (pin "6") (pinfunction "6_6") (pintype "passive"))
    )
    (net (code "41") (name "CANRX") (class "Default")
      (node (ref "R7") (pin "2") (pinfunction "2_2") (pintype "passive"))
      (node (ref "U$2") (pin "P$14") (pinfunction "O1_P$14") (pintype "bidirectional"))
    )
    (net (code "42") (name "CANTX") (class "Default")
      (node (ref "R6") (pin "2") (pinfunction "2_2") (pintype "passive"))
      (node (ref "U$2") (pin "P$13") (pinfunction "I2_P$13") (pintype "bidirectional"))
    )
    (net (code "43") (name "CAR+5V") (class "Default")
      (node (ref "C17") (pin "1") (pinfunction "1_1") (pintype "passive"))
      (node (ref "C6") (pin "1") (pinfunction "1_1") (pintype "passive"))
      (node (ref "C7") (pin "1") (pinfunction "1_1") (pintype "passive"))
      (node (ref "IC5") (pin "3") (pinfunction "VDD_3") (pintype "bidirectional"))
      (node (ref "JP1") (pin "1") (pinfunction "1_1") (pintype "passive"))
      (node (ref "REG5_C3") (pin "1") (pinfunction "1_1") (pintype "passive"))
      (node (ref "REG5_C5") (pin "1") (pinfunction "1_1") (pintype "passive"))
      (node (ref "REG5_D1") (pin "A") (pinfunction "A_A") (pintype "passive"))
      (node (ref "REG5_L") (pin "2") (pinfunction "2_2") (pintype "passive"))
      (node (ref "REG5_R2") (pin "2") (pinfunction "2_2") (pintype "passive"))
      (node (ref "U$2") (pin "P$1") (pinfunction "VDD_P$1") (pintype "bidirectional"))
      (node (ref "U$2") (pin "P$6") (pinfunction "RCSEL_P$6") (pintype "bidirectional"))
      (node (ref "U$2") (pin "P$7") (pinfunction "EN1_P$7") (pintype "bidirectional"))
    )
    (net (code "44") (name "CARGND") (class "Default")
      (node (ref "C17") (pin "2") (pinfunction "2_2") (pintype "passive"))
      (node (ref "C6") (pin "2") (pinfunction "2_2") (pintype "passive"))
      (node (ref "C7") (pin "2") (pinfunction "2_2") (pintype "passive"))
      (node (ref "IC3") (pin "2") (pinfunction "GND_2") (pintype "bidirectional"))
      (node (ref "IC5") (pin "2") (pinfunction "VSS_2") (pintype "bidirectional"))
      (node (ref "R39") (pin "2") (pinfunction "2_2") (pintype "passive"))
      (node (ref "REG5_C1") (pin "2") (pinfunction "2_2") (pintype "passive"))
      (node (ref "REG5_C3") (pin "2") (pinfunction "2_2") (pintype "passive"))
      (node (ref "REG5_C4") (pin "2") (pinfunction "2_2") (pintype "passive"))
      (node (ref "REG5_C5") (pin "2") (pinfunction "2_2") (pintype "passive"))
      (node (ref "REG5_D2") (pin "2") (pinfunction "A_2") (pintype "passive"))
      (node (ref "REG5_R1") (pin "1") (pinfunction "1_1") (pintype "passive"))
      (node (ref "RV1") (pin "2") (pinfunction "2_2") (pintype "passive"))
      (node (ref "RV2") (pin "2") (pinfunction "2_2") (pintype "passive"))
      (node (ref "RV3") (pin "2") (pinfunction "2_2") (pintype "passive"))
      (node (ref "U$2") (pin "P$2") (pinfunction "GND_P$2") (pintype "bidirectional"))
      (node (ref "U$2") (pin "P$5") (pinfunction "RCIN_P$5") (pintype "bidirectional"))
      (node (ref "U$2") (pin "P$8") (pinfunction "GND_P$8") (pintype "bidirectional"))
      (node (ref "X7") (pin "4") (pinfunction "4_4") (pintype "passive"))
      (node (ref "X7") (pin "8") (pinfunction "8_8") (pintype "passive"))
    )
    (net (code "45") (name "CARVIN") (class "Default")
      (node (ref "L2") (pin "1") (pinfunction "1_1") (pintype "passive"))
      (node (ref "REG5_C4") (pin "1") (pinfunction "1_1") (pintype "passive"))
      (node (ref "RV1") (pin "1") (pinfunction "1_1") (pintype "passive"))
      (node (ref "X7") (pin "1") (pinfunction "1_1") (pintype "passive"))
      (node (ref "X7") (pin "5") (pinfunction "5_5") (pintype "passive"))
    )
    (net (code "46") (name "CSB") (class "Default")
      (node (ref "IC2") (pin "44") (pinfunction "CSBI_44") (pintype "bidirectional"))
      (node (ref "R1") (pin "2") (pinfunction "2_2") (pintype "passive"))
    )
    (net (code "47") (name "FSM") (class "Default")
      (node (ref "C2") (pin "1") (pinfunction "1_1") (pintype "passive"))
      (node (ref "IC2") (pin "29") (pinfunction "VTEMP1_29") (pintype "bidirectional"))
      (node (ref "R59") (pin "1") (pinfunction "1_1") (pintype "passive"))
      (node (ref "R60") (pin "2") (pinfunction "2_2") (pintype "passive"))
    )
    (net (code "48") (name "GND") (class "Default")
      (node (ref "C1") (pin "2") (pinfunction "2_2") (pintype "passive"))
      (node (ref "C14") (pin "1") (pinfunction "1_1") (pintype "passive"))
      (node (ref "C15") (pin "1") (pinfunction "1_1") (pintype "passive"))
      (node (ref "C2") (pin "2") (pinfunction "2_2") (pintype "passive"))
      (node (ref "C22") (pin "2") (pinfunction "2_2") (pintype "passive"))
      (node (ref "C23") (pin "2") (pinfunction "2_2") (pintype "passive"))
      (node (ref "C27") (pin "2") (pinfunction "2_2") (pintype "passive"))
      (node (ref "C3") (pin "2") (pinfunction "2_2") (pintype "passive"))
      (node (ref "C34") (pin "2") (pinfunction "2_2") (pintype "passive"))
      (node (ref "C5") (pin "2") (pinfunction "2_2") (pintype "passive"))
      (node (ref "CVREF") (pin "1") (pinfunction "1_1") (pintype "passive"))
      (node (ref "CVREG") (pin "1") (pinfunction "1_1") (pintype "passive"))
      (node (ref "DT1") (pin "C") (pinfunction "C_C") (pintype "passive"))
      (node (ref "DT2") (pin "C") (pinfunction "C_C") (pintype "passive"))
      (node (ref "DT3") (pin "C") (pinfunction "C_C") (pintype "passive"))
      (node (ref "DT4") (pin "C") (pinfunction "C_C") (pintype "passive"))
      (node (ref "DT5") (pin "C") (pinfunction "C_C") (pintype "passive"))
      (node (ref "DT6") (pin "C") (pinfunction "C_C") (pintype "passive"))
      (node (ref "IC1") (pin "41") (pinfunction "VSS_41") (pintype "bidirectional"))
      (node (ref "IC1") (pin "5") (pinfunction "VSS_5") (pintype "bidirectional"))
      (node (ref "IC2") (pin "27") (pinfunction "V-_27") (pintype "bidirectional"))
      (node (ref "IC2") (pin "33") (pinfunction "TOS_33") (pintype "bidirectional"))
      (node (ref "IC2") (pin "34") (pinfunction "WDTB_34") (pintype "bidirectional"))
      (node (ref "IC2") (pin "35") (pinfunction "GPIO1_35") (pintype "bidirectional"))
      (node (ref "IC2") (pin "36") (pinfunction "GPIO2_36") (pintype "bidirectional"))
      (node (ref "IC2") (pin "37") (pinfunction "A0_37") (pintype "bidirectional"))
      (node (ref "IC2") (pin "38") (pinfunction "A1_38") (pintype "bidirectional"))
      (node (ref "IC2") (pin "39") (pinfunction "A2_39") (pintype "bidirectional"))
      (node (ref "IC2") (pin "40") (pinfunction "A3_40") (pintype "bidirectional"))
      (node (ref "J1") (pin "6") (pinfunction "6_6") (pintype "passive"))
      (node (ref "NTC_C1") (pin "2") (pinfunction "2_2") (pintype "passive"))
      (node (ref "NTC_C2") (pin "2") (pinfunction "2_2") (pintype "passive"))
      (node (ref "NTC_C3") (pin "2") (pinfunction "2_2") (pintype "passive"))
      (node (ref "NTC_C4") (pin "2") (pinfunction "2_2") (pintype "passive"))
      (node (ref "Q2") (pin "2") (pinfunction "S_2") (pintype "passive"))
      (node (ref "R11") (pin "1") (pinfunction "1_1") (pintype "passive"))
      (node (ref "R60") (pin "1") (pinfunction "1_1") (pintype "passive"))
      (node (ref "RGQ1_3") (pin "1") (pinfunction "1_1") (pintype "passive"))
      (node (ref "U$2") (pin "P$11") (pinfunction "VSEL_P$11") (pintype "bidirectional"))
      (node (ref "U$2") (pin "P$15") (pinfunction "GNDISO_P$15") (pintype "bidirectional"))
      (node (ref "U$2") (pin "P$9") (pinfunction "GNDISO_P$9") (pintype "bidirectional"))
      (node (ref "V-R") (pin "2") (pinfunction "2_2") (pintype "passive"))
      (node (ref "X1") (pin "3") (pinfunction "3_3") (pintype "passive"))
      (node (ref "Y1") (pin "P2") (pinfunction "GND_P2") (pintype "bidirectional"))
      (node (ref "Y1") (pin "P4") (pinfunction "GND1_P4") (pintype "bidirectional"))
    )
    (net (code "49") (name "ISP_CAN") (class "Default")
      (node (ref "IC1") (pin "14") (pinfunction "PIO0_3_14") (pintype "bidirectional"))
      (node (ref "R11") (pin "2") (pinfunction "2_2") (pintype "passive"))
    )
    (net (code "50") (name "ISP_ENTER") (class "Default")
      (node (ref "IC1") (pin "4") (pinfunction "PIO0_1/CLKOUT/CT32B0_MAT2_4") (pintype "bidirectional"))
      (node (ref "J1") (pin "5") (pinfunction "5_5") (pintype "passive"))
      (node (ref "R15") (pin "2") (pinfunction "2_2") (pintype "passive"))
    )
    (net (code "51") (name "LED1") (class "Default")
      (node (ref "IC1") (pin "24") (pinfunction "PIO2_9_24") (pintype "bidirectional"))
      (node (ref "LED1") (pin "C") (pinfunction "C_C") (pintype "passive"))
    )
    (net (code "52") (name "LED2") (class "Default")
      (node (ref "IC1") (pin "25") (pinfunction "PIO2_10_25") (pintype "bidirectional"))
      (node (ref "LED2") (pin "C") (pinfunction "C_C") (pintype "passive"))
    )
    (net (code "53") (name "MISO0") (class "Default")
      (node (ref "IC1") (pin "27") (pinfunction "PIO0_8/MISO0/CT16B0_MAT0_27") (pintype "bidirectional"))
      (node (ref "R4") (pin "1") (pinfunction "1_1") (pintype "passive"))
    )
    (net (code "54") (name "MISO1") (class "Default")
      (node (ref "IC1") (pin "26") (pinfunction "PIO2_2/~{DCD}/MISO1_26") (pintype "bidirectional"))
    )
    (net (code "55") (name "MOSI0") (class "Default")
      (node (ref "IC1") (pin "28") (pinfunction "PIO0_9/MOSI0/CT16B0_MAT1_28") (pintype "bidirectional"))
      (node (ref "R5") (pin "1") (pinfunction "1_1") (pintype "passive"))
    )
    (net (code "56") (name "MOSI1") (class "Default")
      (node (ref "IC1") (pin "38") (pinfunction "PIO2_3/~{RI}/MOSI1_38") (pintype "bidirectional"))
    )
    (net (code "57") (name "Net-(IC1-CANRX)") (class "Default")
      (node (ref "IC1") (pin "19") (pinfunction "CANRX_19") (pintype "bidirectional"))
      (node (ref "R7") (pin "1") (pinfunction "1_1") (pintype "passive"))
    )
    (net (code "58") (name "Net-(IC1-CANTX)") (class "Default")
      (node (ref "IC1") (pin "20") (pinfunction "CANTX_20") (pintype "bidirectional"))
      (node (ref "R6") (pin "1") (pinfunction "1_1") (pintype "passive"))
    )
    (net (code "59") (name "Net-(IC1-XTALIN)") (class "Default")
      (node (ref "C15") (pin "2") (pinfunction "2_2") (pintype "passive"))
      (node (ref "IC1") (pin "6") (pinfunction "XTALIN_6") (pintype "bidirectional"))
      (node (ref "Y1") (pin "P3") (pinfunction "2_P3") (pintype "passive"))
    )
    (net (code "60") (name "Net-(IC1-XTALOUT)") (class "Default")
      (node (ref "C14") (pin "2") (pinfunction "2_2") (pintype "passive"))
      (node (ref "IC1") (pin "7") (pinfunction "XTALOUT_7") (pintype "bidirectional"))
      (node (ref "Y1") (pin "P1") (pinfunction "1_P1") (pintype "passive"))
    )
    (net (code "61") (name "Net-(IC3-BOOST)") (class "Default")
      (node (ref "IC3") (pin "1") (pinfunction "BOOST_1") (pintype "bidirectional"))
      (node (ref "REG5_C2") (pin "1") (pinfunction "1_1") (pintype "passive"))
      (node (ref "REG5_D1") (pin "C") (pinfunction "C_C") (pintype "passive"))
    )
    (net (code "62") (name "Net-(IC3-FB)") (class "Default")
      (node (ref "IC3") (pin "3") (pinfunction "FB_3") (pintype "bidirectional"))
      (node (ref "REG5_R1") (pin "2") (pinfunction "2_2") (pintype "passive"))
      (node (ref "REG5_R2") (pin "1") (pinfunction "1_1") (pintype "passive"))
    )
    (net (code "63") (name "Net-(IC3-SW)") (class "Default")
      (node (ref "IC3") (pin "6") (pinfunction "SW_6") (pintype "bidirectional"))
      (node (ref "REG5_C2") (pin "2") (pinfunction "2_2") (pintype "passive"))
      (node (ref "REG5_D2") (pin "1") (pinfunction "C_1") (pintype "passive"))
      (node (ref "REG5_L") (pin "1") (pinfunction "1_1") (pintype "passive"))
    )
    (net (code "64") (name "Net-(IC3-VIN)") (class "Default")
      (node (ref "IC3") (pin "4") (pinfunction "~{SHDN}_4") (pintype "bidirectional"))
      (node (ref "IC3") (pin "5") (pinfunction "VIN_5") (pintype "bidirectional"))
      (node (ref "L2") (pin "2") (pinfunction "2_2") (pintype "passive"))
      (node (ref "REG5_C1") (pin "1") (pinfunction "1_1") (pintype "passive"))
    )
    (net (code "65") (name "Net-(IC5-CANH)") (class "Default")
      (node (ref "IC5") (pin "7") (pinfunction "CANH_7") (pintype "bidirectional"))
      (node (ref "L12") (pin "1") (pinfunction "3_1") (pintype "passive"))
    )
    (net (code "66") (name "Net-(IC5-CANL)") (class "Default")
      (node (ref "IC5") (pin "6") (pinfunction "CANL_6") (pintype "bidirectional"))
      (node (ref "L12") (pin "2") (pinfunction "1_2") (pintype "passive"))
    )
    (net (code "67") (name "Net-(IC5-RS)") (class "Default")
      (node (ref "IC5") (pin "8") (pinfunction "RS_8") (pintype "bidirectional"))
      (node (ref "R39") (pin "1") (pinfunction "1_1") (pintype "passive"))
    )
    (net (code "68") (name "Net-(IC5-RX)") (class "Default")
      (node (ref "IC5") (pin "4") (pinfunction "RX_4") (pintype "bidirectional"))
      (node (ref "R41") (pin "1") (pinfunction "1_1") (pintype "passive"))
    )
    (net (code "69") (name "Net-(IC5-TX)") (class "Default")
      (node (ref "IC5") (pin "1") (pinfunction "TX_1") (pintype "bidirectional"))
      (node (ref "R40") (pin "1") (pinfunction "1_1") (pintype "passive"))
    )
    (net (code "70") (name "Net-(L7-Pad2)") (class "Default")
      (node (ref "L7") (pin "2") (pinfunction "2_2") (pintype "passive"))
      (node (ref "V+R") (pin "1") (pinfunction "1_1") (pintype "passive"))
    )
    (net (code "71") (name "Net-(LED1-PadA)") (class "Default")
      (node (ref "LED1") (pin "A") (pinfunction "A_A") (pintype "passive"))
      (node (ref "R2") (pin "1") (pinfunction "1_1") (pintype "passive"))
    )
    (net (code "72") (name "Net-(LED2-PadA)") (class "Default")
      (node (ref "LED2") (pin "A") (pinfunction "A_A") (pintype "passive"))
      (node (ref "R8") (pin "1") (pinfunction "1_1") (pintype "passive"))
    )
    (net (code "73") (name "Net-(Q1-G)") (class "Default")
      (node (ref "D2") (pin "A") (pinfunction "A_A") (pintype "passive"))
      (node (ref "Q1") (pin "1") (pinfunction "G_1") (pintype "passive"))
      (node (ref "RGQ1_1") (pin "2") (pinfunction "2_2") (pintype "passive"))
      (node (ref "RGQ1_2") (pin "2") (pinfunction "2_2") (pintype "passive"))
    )
    (net (code "74") (name "Net-(Q1-S)") (class "Default")
      (node (ref "D1") (pin "C") (pinfunction "C_C") (pintype "passive"))
      (node (ref "D2") (pin "C") (pinfunction "C_C") (pintype "passive"))
      (node (ref "Q1") (pin "2") (pinfunction "S_2") (pintype "passive"))
      (node (ref "RGQ1_1") (pin "1") (pinfunction "1_1") (pintype "passive"))
      (node (ref "V+R") (pin "2") (pinfunction "2_2") (pintype "passive"))
    )
    (net (code "75") (name "Net-(Q2-D)") (class "Default")
      (node (ref "Q2") (pin "3") (pinfunction "D_3") (pintype "passive"))
      (node (ref "RGQ1_2") (pin "1") (pinfunction "1_1") (pintype "passive"))
    )
    (net (code "76") (name "Net-(QB1-D)") (class "Default")
      (node (ref "QB1") (pin "3") (pinfunction "D_3") (pintype "passive"))
      (node (ref "RP1") (pin "2") (pinfunction "2_2") (pintype "passive"))
    )
    (net (code "77") (name "Net-(QB1-G)") (class "Default")
      (node (ref "QB1") (pin "1") (pinfunction "G_1") (pintype "passive"))
      (node (ref "RBG1") (pin "1") (pinfunction "1_1") (pintype "passive"))
    )
    (net (code "78") (name "Net-(QB2-D)") (class "Default")
      (node (ref "QB2") (pin "3") (pinfunction "D_3") (pintype "passive"))
      (node (ref "RP2") (pin "2") (pinfunction "2_2") (pintype "passive"))
    )
    (net (code "79") (name "Net-(QB2-G)") (class "Default")
      (node (ref "QB2") (pin "1") (pinfunction "G_1") (pintype "passive"))
      (node (ref "RBG2") (pin "1") (pinfunction "1_1") (pintype "passive"))
    )
    (net (code "80") (name "Net-(QB3-D)") (class "Default")
      (node (ref "QB3") (pin "3") (pinfunction "D_3") (pintype "passive"))
      (node (ref "RP3") (pin "2") (pinfunction "2_2") (pintype "passive"))
    )
    (net (code "81") (name "Net-(QB3-G)") (class "Default")
      (node (ref "QB3") (pin "1") (pinfunction "G_1") (pintype "passive"))
      (node (ref "RBG3") (pin "1") (pinfunction "1_1") (pintype "passive"))
    )
    (net (code "82") (name "Net-(QB4-D)") (class "Default")
      (node (ref "QB4") (pin "3") (pinfunction "D_3") (pintype "passive"))
      (node (ref "RP4") (pin "2") (pinfunction "2_2") (pintype "passive"))
    )
    (net (code "83") (name "Net-(QB4-G)") (class "Default")
      (node (ref "QB4") (pin "1") (pinfunction "G_1") (pintype "passive"))
      (node (ref "RBG4") (pin "1") (pinfunction "1_1") (pintype "passive"))
    )
    (net (code "84") (name "Net-(QB5-D)") (class "Default")
      (node (ref "QB5") (pin "3") (pinfunction "D_3") (pintype "passive"))
      (node (ref "RP5") (pin "2") (pinfunction "2_2") (pintype "passive"))
    )
    (net (code "85") (name "Net-(QB5-G)") (class "Default")
      (node (ref "QB5") (pin "1") (pinfunction "G_1") (pintype "passive"))
      (node (ref "RBG5") (pin "1") (pinfunction "1_1") (pintype "passive"))
    )
    (net (code "86") (name "Net-(QB6-D)") (class "Default")
      (node (ref "QB6") (pin "3") (pinfunction "D_3") (pintype "passive"))
      (node (ref "RP6") (pin "2") (pinfunction "2_2") (pintype "passive"))
    )
    (net (code "87") (name "Net-(QB6-G)") (class "Default")
      (node (ref "QB6") (pin "1") (pinfunction "G_1") (pintype "passive"))
      (node (ref "RBG6") (pin "1") (pinfunction "1_1") (pintype "passive"))
    )
    (net (code "88") (name "Net-(QB7-D)") (class "Default")
      (node (ref "QB7") (pin "3") (pinfunction "D_3") (pintype "passive"))
      (node (ref "RP7") (pin "2") (pinfunction "2_2") (pintype "passive"))
    )
    (net (code "89") (name "Net-(QB7-G)") (class "Default")
      (node (ref "QB7") (pin "1") (pinfunction "G_1") (pintype "passive"))
      (node (ref "RBG7") (pin "1") (pinfunction "1_1") (pintype "passive"))
    )
    (net (code "90") (name "Net-(QB8-D)") (class "Default")
      (node (ref "QB8") (pin "3") (pinfunction "D_3") (pintype "passive"))
      (node (ref "RP8") (pin "2") (pinfunction "2_2") (pintype "passive"))
    )
    (net (code "91") (name "Net-(QB8-G)") (class "Default")
      (node (ref "QB8") (pin "1") (pinfunction "G_1") (pintype "passive"))
      (node (ref "RBG8") (pin "1") (pinfunction "1_1") (pintype "passive"))
    )
    (net (code "92") (name "Net-(QB9-D)") (class "Default")
      (node (ref "QB9") (pin "3") (pinfunction "D_3") (pintype "passive"))
      (node (ref "RP9") (pin "2") (pinfunction "2_2") (pintype "passive"))
    )
    (net (code "93") (name "Net-(QB9-G)") (class "Default")
      (node (ref "QB9") (pin "1") (pinfunction "G_1") (pintype "passive"))
      (node (ref "RBG9") (pin "1") (pinfunction "1_1") (pintype "passive"))
    )
    (net (code "94") (name "Net-(QB10-D)") (class "Default")
      (node (ref "QB10") (pin "3") (pinfunction "D_3") (pintype "passive"))
      (node (ref "RP10") (pin "2") (pinfunction "2_2") (pintype "passive"))
    )
    (net (code "95") (name "Net-(QB10-G)") (class "Default")
      (node (ref "QB10") (pin "1") (pinfunction "G_1") (pintype "passive"))
      (node (ref "RBG10") (pin "1") (pinfunction "1_1") (pintype "passive"))
    )
    (net (code "96") (name "Net-(QB11-D)") (class "Default")
      (node (ref "QB11") (pin "3") (pinfunction "D_3") (pintype "passive"))
      (node (ref "RP11") (pin "2") (pinfunction "2_2") (pintype "passive"))
    )
    (net (code "97") (name "Net-(QB11-G)") (class "Default")
      (node (ref "QB11") (pin "1") (pinfunction "G_1") (pintype "passive"))
      (node (ref "RBG11") (pin "1") (pinfunction "1_1") (pintype "passive"))
    )
    (net (code "98") (name "Net-(QB12-D)") (class "Default")
      (node (ref "QB12") (pin "3") (pinfunction "D_3") (pintype "passive"))
      (node (ref "RP12") (pin "2") (pinfunction "2_2") (pintype "passive"))
    )
    (net (code "99") (name "Net-(QB12-G)") (class "Default")
      (node (ref "QB12") (pin "1") (pinfunction "G_1") (pintype "passive"))
      (node (ref "RBG12") (pin "1") (pinfunction "1_1") (pintype "passive"))
    )
    (net (code "100") (name "Net-(U$2-I1)") (class "Default")
      (node (ref "R41") (pin "2") (pinfunction "2_2") (pintype "passive"))
      (node (ref "U$2") (pin "P$3") (pinfunction "I1_P$3") (pintype "bidirectional"))
    )
    (net (code "101") (name "Net-(U$2-O2)") (class "Default")
      (node (ref "R40") (pin "2") (pinfunction "2_2") (pintype "passive"))
      (node (ref "U$2") (pin "P$4") (pinfunction "O2_P$4") (pintype "bidirectional"))
    )
    (net (code "102") (name "SCK") (class "Default")
      (node (ref "IC2") (pin "41") (pinfunction "SCKI_41") (pintype "bidirectional"))
      (node (ref "R3") (pin "2") (pinfunction "2_2") (pintype "passive"))
    )
    (net (code "103") (name "SCK0") (class "Default")
      (node (ref "IC1") (pin "22") (pinfunction "PIO0_6/SCK0_22") (pintype "bidirectional"))
      (node (ref "R3") (pin "1") (pinfunction "1_1") (pintype "passive"))
    )
    (net (code "104") (name "SCK1") (class "Default")
      (node (ref "IC1") (pin "13") (pinfunction "PIO2_1/~{DSR}/SCK1_13") (pintype "bidirectional"))
    )
    (net (code "105") (name "SDI") (class "Default")
      (node (ref "IC2") (pin "42") (pinfunction "SDI_42") (pintype "bidirectional"))
      (node (ref "R5") (pin "2") (pinfunction "2_2") (pintype "passive"))
    )
    (net (code "106") (name "SDO") (class "Default")
      (node (ref "IC2") (pin "43") (pinfunction "SDO_43") (pintype "bidirectional"))
      (node (ref "R19") (pin "1") (pinfunction "1_1") (pintype "passive"))
      (node (ref "R4") (pin "2") (pinfunction "2_2") (pintype "passive"))
    )
    (net (code "107") (name "SSEL0") (class "Default")
      (node (ref "IC1") (pin "10") (pinfunction "PIO0_2/SSEL/CT16B0_CAP0_10") (pintype "bidirectional"))
      (node (ref "R1") (pin "1") (pinfunction "1_1") (pintype "passive"))
    )
    (net (code "108") (name "SSEL1") (class "Default")
      (node (ref "IC1") (pin "2") (pinfunction "PIO2_0/~{DTR}/SSEL1_2") (pintype "bidirectional"))
    )
    (net (code "109") (name "SWCLK") (class "Default")
      (node (ref "IC1") (pin "29") (pinfunction "PIO0_10/SWCLK/SCK0/CT16B0_MAT2_29") (pintype "bidirectional"))
      (node (ref "J1") (pin "4") (pinfunction "4_4") (pintype "passive"))
    )
    (net (code "110") (name "SWDIO") (class "Default")
      (node (ref "IC1") (pin "39") (pinfunction "PIO1_3/SWDIO/AD4/CT32B1_MAT2_39") (pintype "bidirectional"))
      (node (ref "J1") (pin "3") (pinfunction "3_3") (pintype "passive"))
    )
    (net (code "111") (name "TEMP0") (class "Default")
      (node (ref "IC1") (pin "42") (pinfunction "PIO1_11/AD7_42") (pintype "bidirectional"))
      (node (ref "NTC_C3") (pin "1") (pinfunction "1_1") (pintype "passive"))
      (node (ref "NTC_R3") (pin "1") (pinfunction "1_1") (pintype "passive"))
      (node (ref "X1") (pin "1") (pinfunction "2_1") (pintype "passive"))
    )
    (net (code "112") (name "TEMP1") (class "Default")
      (node (ref "IC1") (pin "40") (pinfunction "PIO1_4/AD5/CT32B1_MAT3_40") (pintype "bidirectional"))
      (node (ref "NTC_C2") (pin "1") (pinfunction "1_1") (pintype "passive"))
      (node (ref "NTC_R2") (pin "1") (pinfunction "1_1") (pintype "passive"))
      (node (ref "X1") (pin "2") (pinfunction "1_2") (pintype "passive"))
    )
    (net (code "113") (name "TEMP2") (class "Default")
      (node (ref "IC1") (pin "35") (pinfunction "PIO1_2/AD3/CT32B1_MAT1_35") (pintype "bidirectional"))
      (node (ref "NTC_C4") (pin "1") (pinfunction "1_1") (pintype "passive"))
      (node (ref "NTC_R4") (pin "1") (pinfunction "1_1") (pintype "passive"))
      (node (ref "X1") (pin "4") (pinfunction "4_4") (pintype "passive"))
    )
    (net (code "114") (name "TEMP3") (class "Default")
      (node (ref "IC1") (pin "34") (pinfunction "PIO1_1/AD2/CT32B1_MAT0_34") (pintype "bidirectional"))
      (node (ref "NTC_C1") (pin "1") (pinfunction "1_1") (pintype "passive"))
      (node (ref "NTC_R1") (pin "1") (pinfunction "1_1") (pintype "passive"))
      (node (ref "X1") (pin "5") (pinfunction "5_5") (pintype "passive"))
    )
    (net (code "115") (name "TEMPR") (class "Default")
      (node (ref "C3") (pin "1") (pinfunction "1_1") (pintype "passive"))
      (node (ref "DT1") (pin "A") (pinfunction "A_A") (pintype "passive"))
      (node (ref "DT2") (pin "A") (pinfunction "A_A") (pintype "passive"))
      (node (ref "DT3") (pin "A") (pinfunction "A_A") (pintype "passive"))
      (node (ref "DT4") (pin "A") (pinfunction "A_A") (pintype "passive"))
      (node (ref "DT5") (pin "A") (pinfunction "A_A") (pintype "passive"))
      (node (ref "DT6") (pin "A") (pinfunction "A_A") (pintype "passive"))
      (node (ref "IC1") (pin "33") (pinfunction "PIO1_0/AD1/CT32B1_CAP0_33") (pintype "bidirectional"))
      (node (ref "R9") (pin "1") (pinfunction "1_1") (pintype "passive"))
    )
    (net (code "116") (name "V+") (class "Default")
      (node (ref "C1") (pin "1") (pinfunction "1_1") (pintype "passive"))
      (node (ref "IC2") (pin "1") (pinfunction "V+_1") (pintype "bidirectional"))
      (node (ref "Q1") (pin "3") (pinfunction "D_3") (pintype "passive"))
      (node (ref "R59") (pin "2") (pinfunction "2_2") (pintype "passive"))
    )
    (net (code "117") (name "VREF") (class "Default")
      (node (ref "CVREF") (pin "2") (pinfunction "2_2") (pintype "passive"))
      (node (ref "IC2") (pin "31") (pinfunction "VREF_31") (pintype "bidirectional"))
    )
    (net (code "118") (name "VREG") (class "Default")
      (node (ref "CVREG") (pin "2") (pinfunction "2_2") (pintype "passive"))
      (node (ref "IC2") (pin "32") (pinfunction "VREG_32") (pintype "bidirectional"))
    )
    (net (code "119") (name "unconnected-(IC1-PIO0_4{slash}SCL-Pad15)") (class "Default")
      (node (ref "IC1") (pin "15") (pinfunction "PIO0_4/SCL_15") (pintype "bidirectional"))
    )
    (net (code "120") (name "unconnected-(IC1-PIO0_5{slash}SDA-Pad16)") (class "Default")
      (node (ref "IC1") (pin "16") (pinfunction "PIO0_5/SDA_16") (pintype "bidirectional"))
    )
    (net (code "121") (name "unconnected-(IC1-PIO0_7{slash}~{CTS}-Pad23)") (class "Default")
      (node (ref "IC1") (pin "23") (pinfunction "PIO0_7/~{CTS}_23") (pintype "bidirectional"))
    )
    (net (code "122") (name "unconnected-(IC1-PIO0_11{slash}AD0{slash}CT32B0_MAT3-Pad32)") (class "Default")
      (node (ref "IC1") (pin "32") (pinfunction "PIO0_11/AD0/CT32B0_MAT3_32") (pintype "bidirectional"))
    )
    (net (code "123") (name "unconnected-(IC1-PIO1_5{slash}~{RTS}{slash}CT32B0_CAP0-Pad45)") (class "Default")
      (node (ref "IC1") (pin "45") (pinfunction "PIO1_5/~{RTS}/CT32B0_CAP0_45") (pintype "bidirectional"))
    )
    (net (code "124") (name "unconnected-(IC1-PIO1_6{slash}RXD{slash}CT32B0_MAT0-Pad46)") (class "Default")
      (node (ref "IC1") (pin "46") (pinfunction "PIO1_6/RXD/CT32B0_MAT0_46") (pintype "bidirectional"))
    )
    (net (code "125") (name "unconnected-(IC1-PIO1_7{slash}TXD{slash}CT32B0_MAT1-Pad47)") (class "Default")
      (node (ref "IC1") (pin "47") (pinfunction "PIO1_7/TXD/CT32B0_MAT1_47") (pintype "bidirectional"))
    )
    (net (code "126") (name "unconnected-(IC1-PIO1_8{slash}CT16B1_CAP0-Pad9)") (class "Default")
      (node (ref "IC1") (pin "9") (pinfunction "PIO1_8/CT16B1_CAP0_9") (pintype "bidirectional"))
    )
    (net (code "127") (name "unconnected-(IC1-PIO1_9{slash}CT16B1_MAT0-Pad17)") (class "Default")
      (node (ref "IC1") (pin "17") (pinfunction "PIO1_9/CT16B1_MAT0_17") (pintype "bidirectional"))
    )
    (net (code "128") (name "unconnected-(IC1-PIO1_10{slash}AD6{slash}CT16B1_MAT1-Pad30)") (class "Default")
      (node (ref "IC1") (pin "30") (pinfunction "PIO1_10/AD6/CT16B1_MAT1_30") (pintype "bidirectional"))
    )
    (net (code "129") (name "unconnected-(IC1-PIO2_4-Pad18)") (class "Default")
      (node (ref "IC1") (pin "18") (pinfunction "PIO2_4_18") (pintype "bidirectional"))
    )
    (net (code "130") (name "unconnected-(IC1-PIO2_5-Pad21)") (class "Default")
      (node (ref "IC1") (pin "21") (pinfunction "PIO2_5_21") (pintype "bidirectional"))
    )
    (net (code "131") (name "unconnected-(IC1-PIO2_6-Pad1)") (class "Default")
      (node (ref "IC1") (pin "1") (pinfunction "PIO2_6_1") (pintype "bidirectional"))
    )
    (net (code "132") (name "unconnected-(IC1-PIO2_7-Pad11)") (class "Default")
      (node (ref "IC1") (pin "11") (pinfunction "PIO2_7_11") (pintype "bidirectional"))
    )
    (net (code "133") (name "unconnected-(IC1-PIO2_8-Pad12)") (class "Default")
      (node (ref "IC1") (pin "12") (pinfunction "PIO2_8_12") (pintype "bidirectional"))
    )
    (net (code "134") (name "unconnected-(IC1-PIO2_11{slash}SCK0-Pad31)") (class "Default")
      (node (ref "IC1") (pin "31") (pinfunction "PIO2_11/SCK0_31") (pintype "bidirectional"))
    )
    (net (code "135") (name "unconnected-(IC1-PIO3_0{slash}~{DTR}-Pad36)") (class "Default")
      (node (ref "IC1") (pin "36") (pinfunction "PIO3_0/~{DTR}_36") (pintype "bidirectional"))
    )
    (net (code "136") (name "unconnected-(IC1-PIO3_1{slash}~{DSR}-Pad37)") (class "Default")
      (node (ref "IC1") (pin "37") (pinfunction "PIO3_1/~{DSR}_37") (pintype "bidirectional"))
    )
    (net (code "137") (name "unconnected-(IC1-PIO3_2{slash}~{DCD}-Pad43)") (class "Default")
      (node (ref "IC1") (pin "43") (pinfunction "PIO3_2/~{DCD}_43") (pintype "bidirectional"))
    )
    (net (code "138") (name "unconnected-(IC1-PIO3_3{slash}~{RI}-Pad48)") (class "Default")
      (node (ref "IC1") (pin "48") (pinfunction "PIO3_3/~{RI}_48") (pintype "bidirectional"))
    )
    (net (code "139") (name "unconnected-(IC5-VRF-Pad5)") (class "Default")
      (node (ref "IC5") (pin "5") (pinfunction "VRF_5") (pintype "bidirectional"))
    )
    (net (code "140") (name "~{RESET}") (class "Default")
      (node (ref "C34") (pin "1") (pinfunction "1_1") (pintype "passive"))
      (node (ref "IC1") (pin "3") (pinfunction "PIO0_0/~{RESET}_3") (pintype "bidirectional"))
      (node (ref "J1") (pin "1") (pinfunction "1_1") (pintype "passive"))
      (node (ref "R52") (pin "2") (pinfunction "2_2") (pintype "passive"))
    )
  )
)
